# BMSV1_1.net
KiCad netlist of a schematic drawn in EAGLE
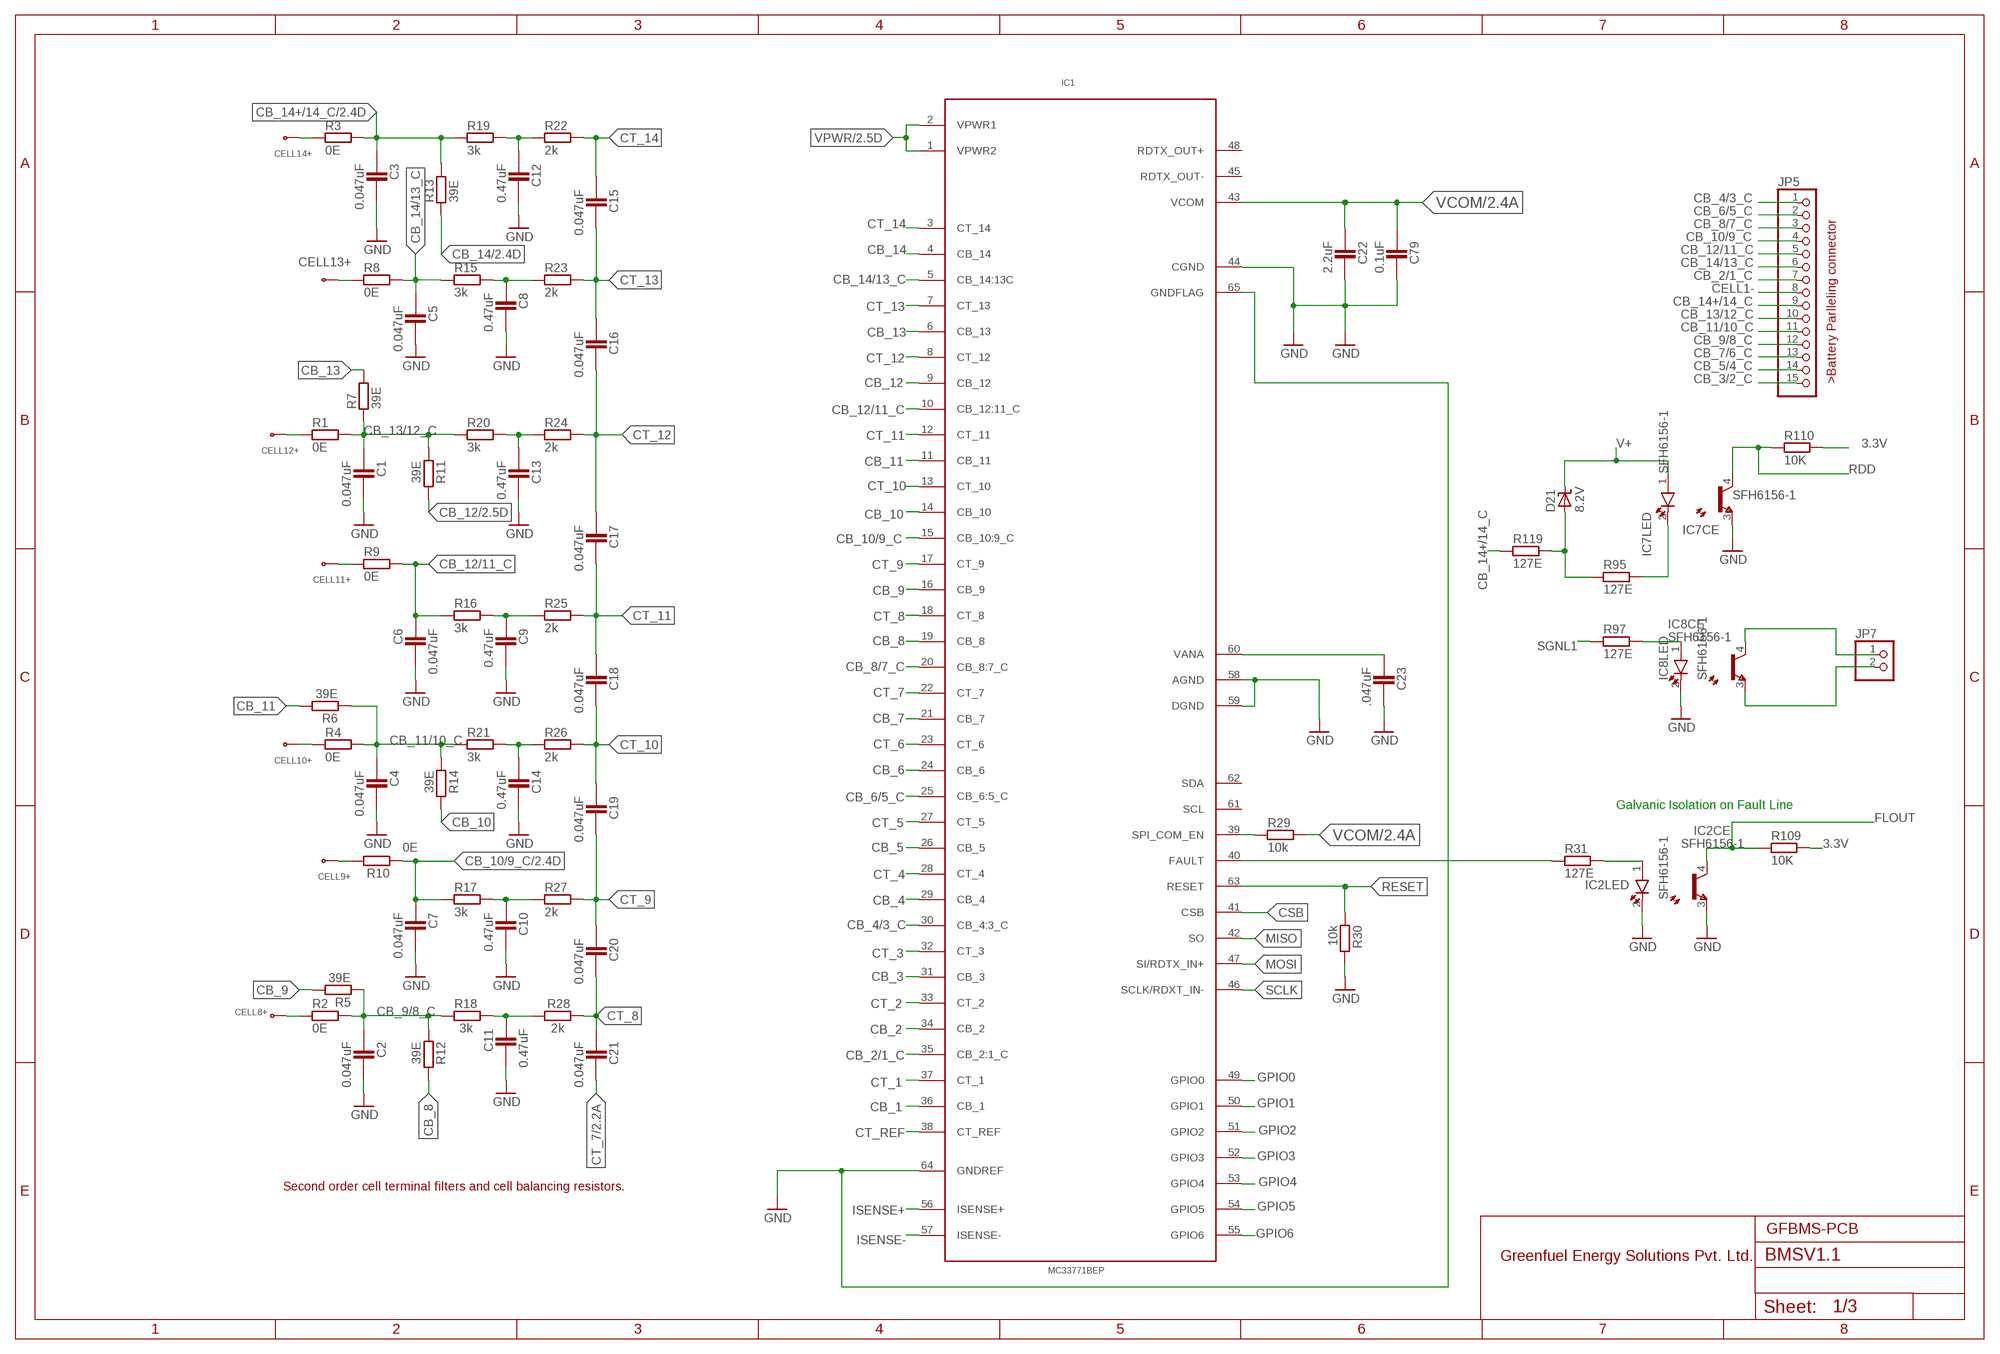
[diagram p0: schematic, sheet 1]
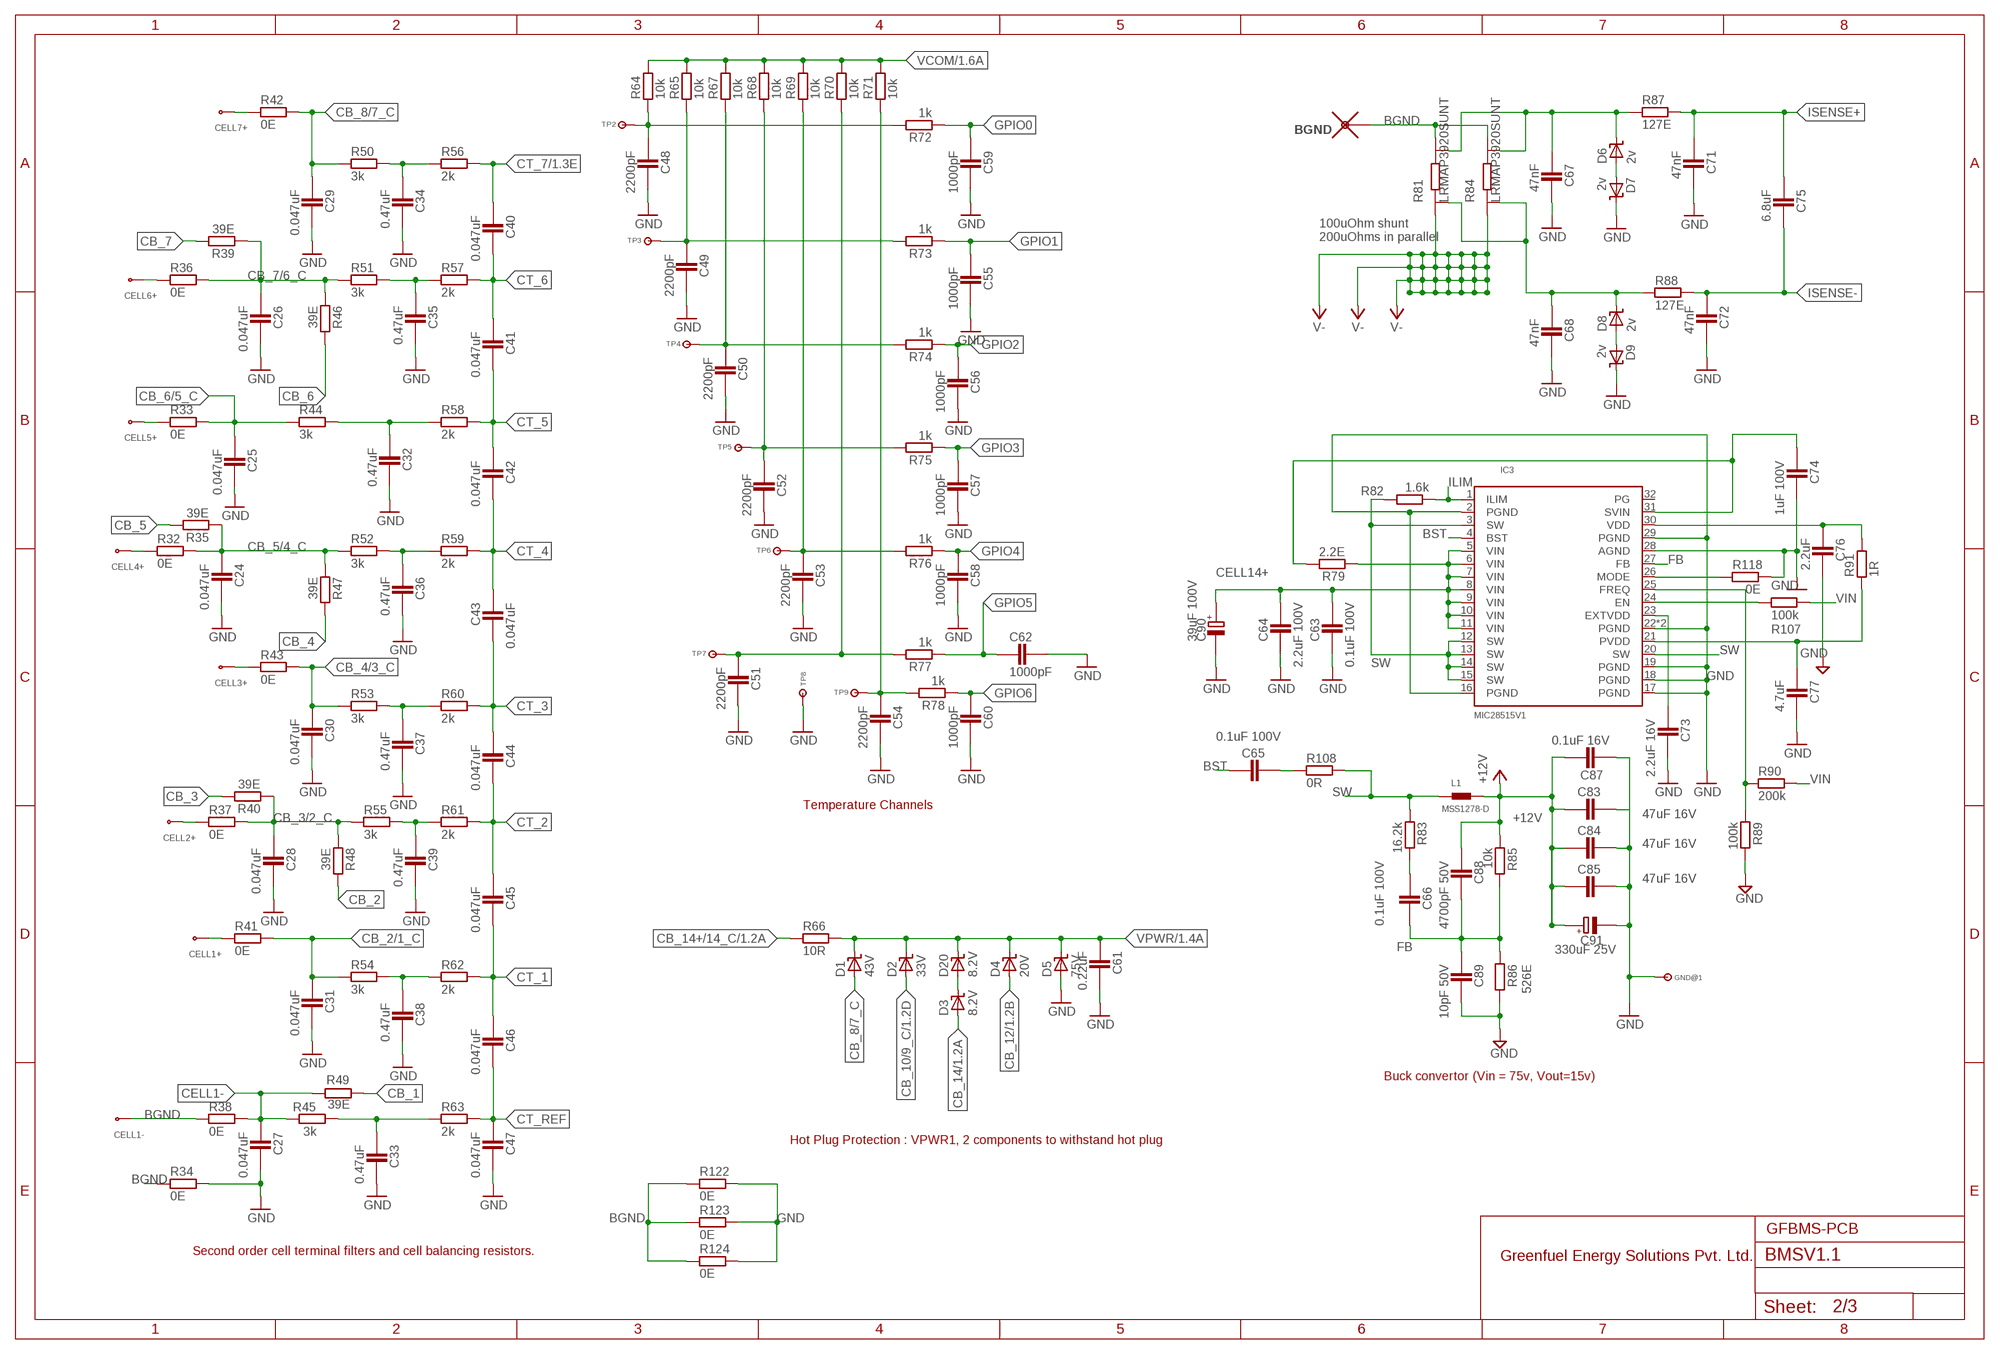
[diagram p1: schematic, sheet 2]
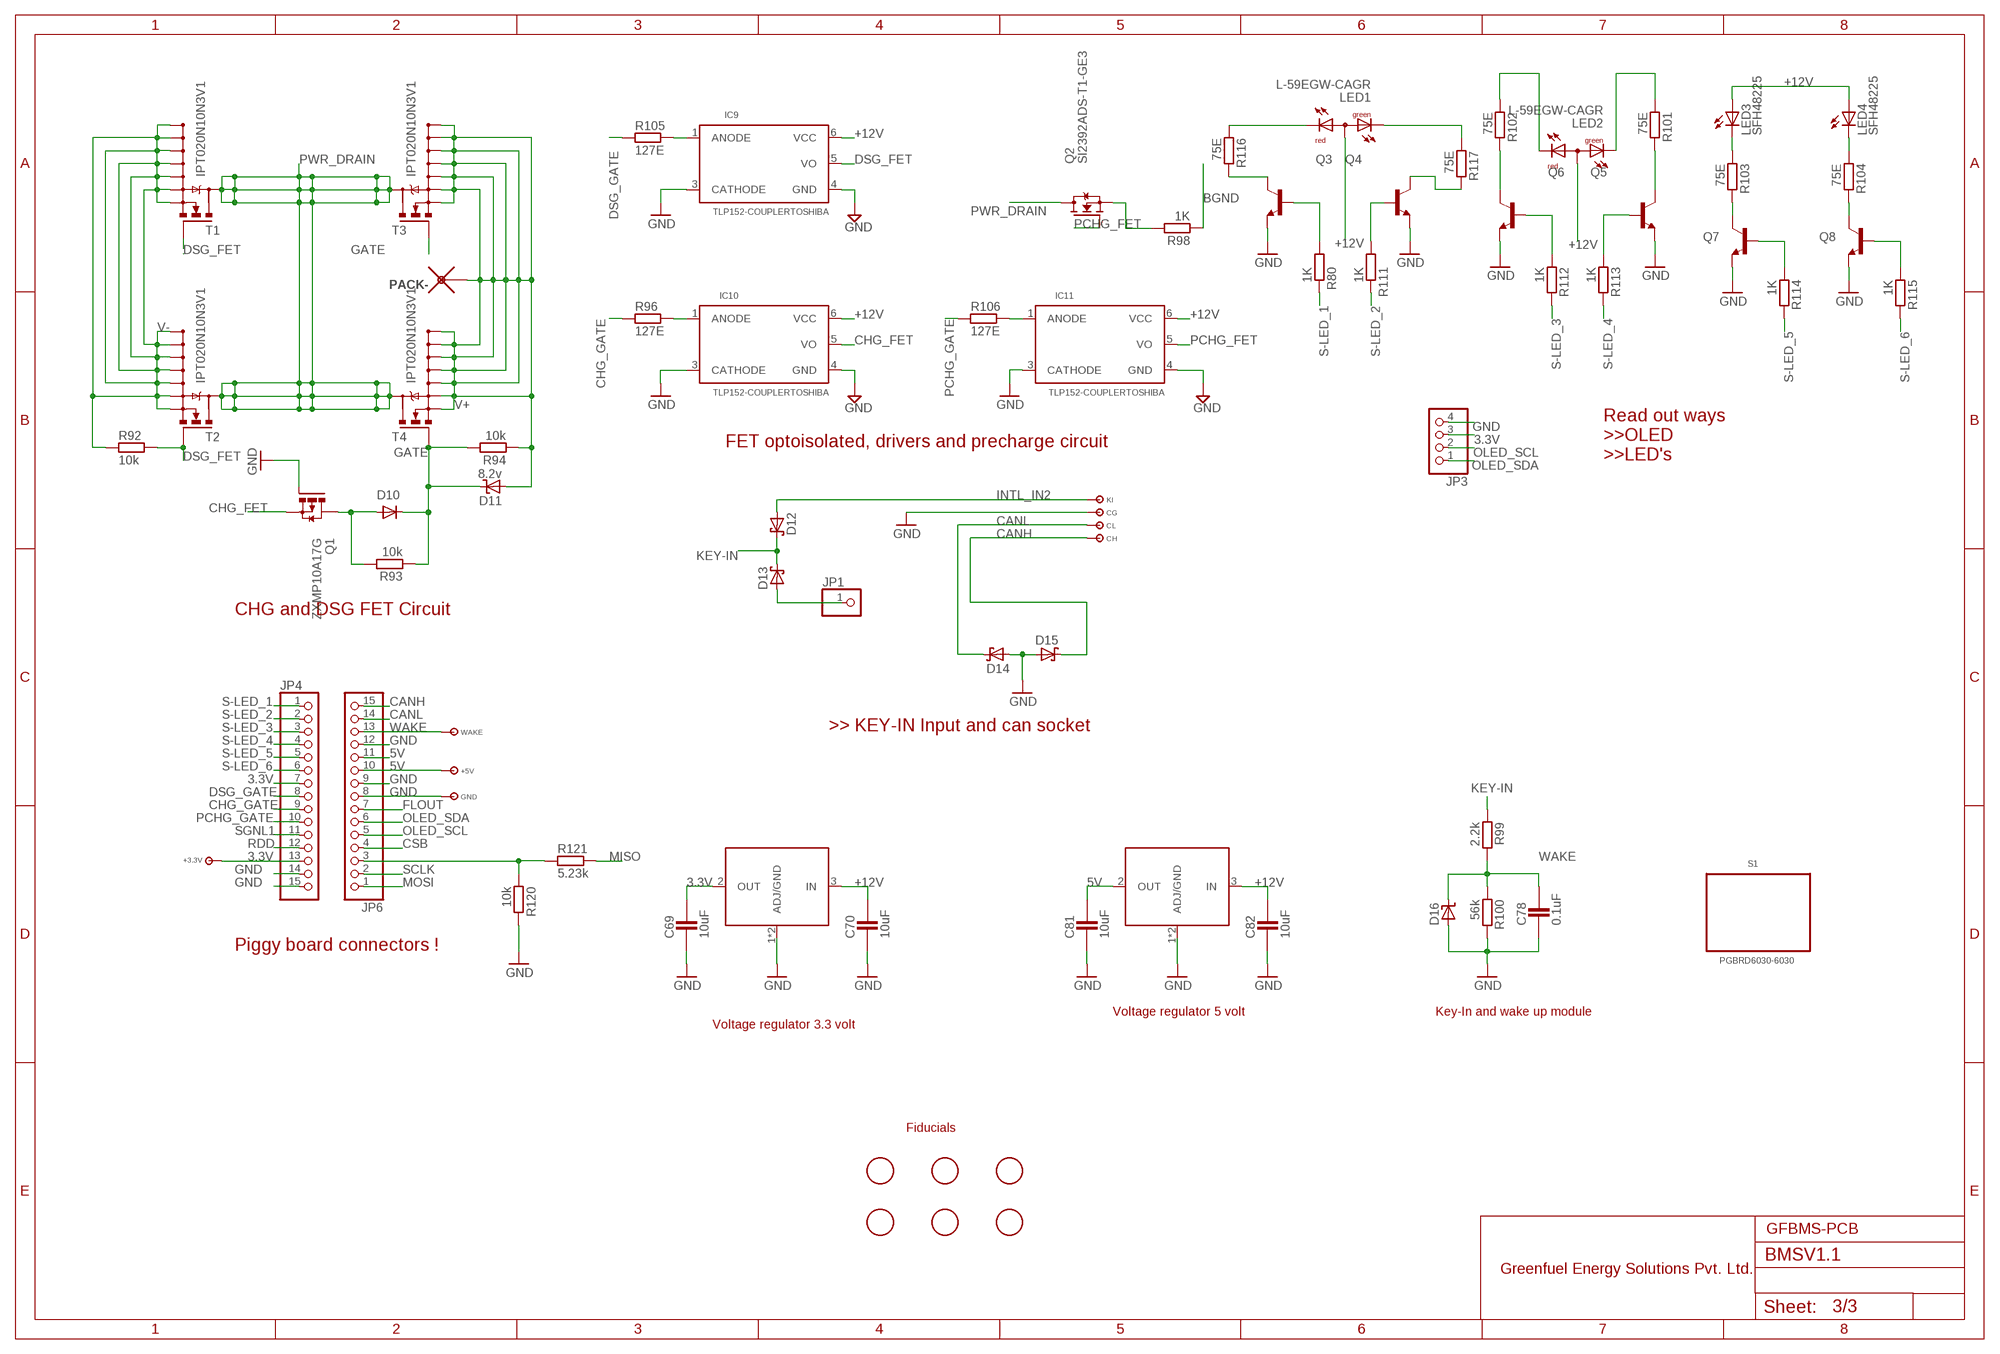
[diagram p2: schematic, sheet 3]

(export (version "E")
  (design (tool "Eeschema 10.0.6"))
  (components
    (comp (ref "+3.3V")
      (value "TP-SMD60")
      (footprint "eagle-import:TP-SMD60")
      (libsource (lib "eagle-import") (part "TP-SMD60"))
    )
    (comp (ref "+5V")
      (value "TP-SMD60")
      (footprint "eagle-import:TP-SMD60")
      (libsource (lib "eagle-import") (part "TP-SMD60"))
    )
    (comp (ref "C69")
      (value "10uF")
      (footprint "eagle-import:CAPC2012X145AN")
      (libsource (lib "eagle-import") (part "CAPACITOR_0805"))
    )
    (comp (ref "C70")
      (value "10uF")
      (footprint "eagle-import:CAPC2012X145AN")
      (libsource (lib "eagle-import") (part "CAPACITOR_0805"))
    )
    (comp (ref "C78")
      (value "0.1uF")
      (footprint "eagle-import:CAPC1608X92N")
      (libsource (lib "eagle-import") (part "CAPACITOR_0603"))
    )
    (comp (ref "C81")
      (value "10uF")
      (footprint "eagle-import:CAPC2012X145AN")
      (libsource (lib "eagle-import") (part "CAPACITOR_0805"))
    )
    (comp (ref "C82")
      (value "10uF")
      (footprint "eagle-import:CAPC2012X145AN")
      (libsource (lib "eagle-import") (part "CAPACITOR_0805"))
    )
    (comp (ref "CG")
      (value "TPTH7035")
      (footprint "eagle-import:TP7035")
      (libsource (lib "eagle-import") (part "TPTH7035"))
    )
    (comp (ref "CH")
      (value "TPTH7035")
      (footprint "eagle-import:TP7035")
      (libsource (lib "eagle-import") (part "TPTH7035"))
    )
    (comp (ref "CL")
      (value "TPTH7035")
      (footprint "eagle-import:TP7035")
      (libsource (lib "eagle-import") (part "TPTH7035"))
    )
    (comp (ref "D10")
      (value "DIODE_SOD-123")
      (footprint "eagle-import:SOD3718X135N")
      (libsource (lib "eagle-import") (part "DIODE_SOD-123"))
    )
    (comp (ref "D11")
      (value "8.2v")
      (footprint "eagle-import:SOD3718X135N")
      (libsource (lib "eagle-import") (part "ZENER_SOD-123"))
    )
    (comp (ref "D12")
      (value "SCHOTTKY_SOD-123")
      (footprint "eagle-import:SOD3718X135N")
      (libsource (lib "eagle-import") (part "SCHOTTKY_SOD-123"))
    )
    (comp (ref "D13")
      (value "SCHOTTKY_SOD-123")
      (footprint "eagle-import:SOD3718X135N")
      (libsource (lib "eagle-import") (part "SCHOTTKY_SOD-123"))
    )
    (comp (ref "D14")
      (value "SCHOTTKY_SOD-123")
      (footprint "eagle-import:SOD3718X135N")
      (libsource (lib "eagle-import") (part "SCHOTTKY_SOD-123"))
    )
    (comp (ref "D15")
      (value "SCHOTTKY_SOD-123")
      (footprint "eagle-import:SOD3718X135N")
      (libsource (lib "eagle-import") (part "SCHOTTKY_SOD-123"))
    )
    (comp (ref "D16")
      (value "ZENER_SOD-323")
      (footprint "eagle-import:SOD2514X100N")
      (libsource (lib "eagle-import") (part "ZENER_SOD-323"))
    )
    (comp (ref "FD1")
      (value "FIDUCIAL")
      (footprint "eagle-import:FIDUCIAL_1MM")
      (libsource (lib "eagle-import") (part "FIDUCIAL"))
    )
    (comp (ref "FD2")
      (value "FIDUCIAL")
      (footprint "eagle-import:FIDUCIAL_1MM")
      (libsource (lib "eagle-import") (part "FIDUCIAL"))
    )
    (comp (ref "FD3")
      (value "FIDUCIAL")
      (footprint "eagle-import:FIDUCIAL_1MM")
      (libsource (lib "eagle-import") (part "FIDUCIAL"))
    )
    (comp (ref "FD4")
      (value "FIDUCIAL")
      (footprint "eagle-import:FIDUCIAL_1MM")
      (libsource (lib "eagle-import") (part "FIDUCIAL"))
    )
    (comp (ref "FD5")
      (value "FIDUCIAL")
      (footprint "eagle-import:FIDUCIAL_1MM")
      (libsource (lib "eagle-import") (part "FIDUCIAL"))
    )
    (comp (ref "FD6")
      (value "FIDUCIAL")
      (footprint "eagle-import:FIDUCIAL_1MM")
      (libsource (lib "eagle-import") (part "FIDUCIAL"))
    )
    (comp (ref "GND")
      (value "TP-SMD60")
      (footprint "eagle-import:TP-SMD60")
      (libsource (lib "eagle-import") (part "TP-SMD60"))
    )
    (comp (ref "IC9")
      (value "TLP152-COUPLERTOSHIBA")
      (footprint "eagle-import:SO6-5PIN")
      (libsource (lib "eagle-import") (part "TLP152-COUPLERTOSHIBA"))
    )
    (comp (ref "IC10")
      (value "TLP152-COUPLERTOSHIBA")
      (footprint "eagle-import:SO6-5PIN")
      (libsource (lib "eagle-import") (part "TLP152-COUPLERTOSHIBA"))
    )
    (comp (ref "IC11")
      (value "TLP152-COUPLERTOSHIBA")
      (footprint "eagle-import:SO6-5PIN")
      (libsource (lib "eagle-import") (part "TLP152-COUPLERTOSHIBA"))
    )
    (comp (ref "JP1")
      (value "PINHD-1X1CB")
      (footprint "eagle-import:1X01-CLEANBIG")
      (libsource (lib "eagle-import") (part "PINHD-1X1CB"))
    )
    (comp (ref "JP3")
      (value "PINOLED-4")
      (footprint "eagle-import:OLED-CON")
      (libsource (lib "eagle-import") (part "PINOLED-4"))
    )
    (comp (ref "JP4")
      (value "PINHD-1X15")
      (footprint "eagle-import:1X15")
      (libsource (lib "eagle-import") (part "PINHD-1X15"))
    )
    (comp (ref "JP6")
      (value "PINHD-1X15")
      (footprint "eagle-import:1X15")
      (libsource (lib "eagle-import") (part "PINHD-1X15"))
    )
    (comp (ref "KI")
      (value "TPTH7035")
      (footprint "eagle-import:TP7035")
      (libsource (lib "eagle-import") (part "TPTH7035"))
    )
    (comp (ref "LED1")
      (value "L-59EGW-CAGR")
      (footprint "eagle-import:L-59EGW-CA")
      (libsource (lib "eagle-import") (part "L-59EGW-CAGR"))
    )
    (comp (ref "LED2")
      (value "L-59EGW-CAGR")
      (footprint "eagle-import:L-59EGW-CA")
      (libsource (lib "eagle-import") (part "L-59EGW-CAGR"))
    )
    (comp (ref "LED3")
      (value "SFH48225")
      (footprint "eagle-import:SFH482")
      (libsource (lib "eagle-import") (part "SFH48225"))
    )
    (comp (ref "LED4")
      (value "SFH48225")
      (footprint "eagle-import:SFH482")
      (libsource (lib "eagle-import") (part "SFH48225"))
    )
    (comp (ref "PACK-")
      (value "WPAD")
      (footprint "eagle-import:WPAD")
      (libsource (lib "eagle-import") (part "WPAD"))
    )
    (comp (ref "Q1")
      (value "ZXMP10A17G")
      (footprint "eagle-import:SOT23-3")
      (libsource (lib "eagle-import") (part "ZXMP10A17G"))
    )
    (comp (ref "Q2")
      (value "SI2392ADS-T1-GE3")
      (footprint "eagle-import:SOT23-3")
      (libsource (lib "eagle-import") (part "BSS138"))
    )
    (comp (ref "Q3")
      (value "NPN_SOT-23")
      (footprint "eagle-import:SOT95P280X135-3N")
      (libsource (lib "eagle-import") (part "NPN_SOT-23"))
    )
    (comp (ref "Q4")
      (value "NPN_SOT-23")
      (footprint "eagle-import:SOT95P280X135-3N")
      (libsource (lib "eagle-import") (part "NPN_SOT-23"))
    )
    (comp (ref "Q5")
      (value "NPN_SOT-23")
      (footprint "eagle-import:SOT95P280X135-3N")
      (libsource (lib "eagle-import") (part "NPN_SOT-23"))
    )
    (comp (ref "Q6")
      (value "NPN_SOT-23")
      (footprint "eagle-import:SOT95P280X135-3N")
      (libsource (lib "eagle-import") (part "NPN_SOT-23"))
    )
    (comp (ref "Q7")
      (value "NPN_SOT-23")
      (footprint "eagle-import:SOT95P280X135-3N")
      (libsource (lib "eagle-import") (part "NPN_SOT-23"))
    )
    (comp (ref "Q8")
      (value "NPN_SOT-23")
      (footprint "eagle-import:SOT95P280X135-3N")
      (libsource (lib "eagle-import") (part "NPN_SOT-23"))
    )
    (comp (ref "R80")
      (value "1K")
      (footprint "eagle-import:RESC1005X40AN")
      (libsource (lib "eagle-import") (part "RESISTOR_0402"))
    )
    (comp (ref "R92")
      (value "10k")
      (footprint "eagle-import:RESC1005X40AN")
      (libsource (lib "eagle-import") (part "RESISTOR_0402"))
    )
    (comp (ref "R93")
      (value "10k")
      (footprint "eagle-import:RESC1005X40AN")
      (libsource (lib "eagle-import") (part "RESISTOR_0402"))
    )
    (comp (ref "R94")
      (value "10k")
      (footprint "eagle-import:RESC1005X40AN")
      (libsource (lib "eagle-import") (part "RESISTOR_0402"))
    )
    (comp (ref "R96")
      (value "127E")
      (footprint "eagle-import:RESC1608X55N")
      (libsource (lib "eagle-import") (part "RESISTOR_0603"))
    )
    (comp (ref "R98")
      (value "1K")
      (footprint "eagle-import:RESC5025X70N")
      (libsource (lib "eagle-import") (part "RESISTOR_2010"))
    )
    (comp (ref "R99")
      (value "2.2k")
      (footprint "eagle-import:RESC1608X55N")
      (libsource (lib "eagle-import") (part "RESISTOR_0603"))
    )
    (comp (ref "R100")
      (value "56k")
      (footprint "eagle-import:RESC1608X55N")
      (libsource (lib "eagle-import") (part "RESISTOR_0603"))
    )
    (comp (ref "R101")
      (value "75E")
      (footprint "eagle-import:RESC1005X40AN")
      (libsource (lib "eagle-import") (part "RESISTOR_0402"))
    )
    (comp (ref "R102")
      (value "75E")
      (footprint "eagle-import:RESC1005X40AN")
      (libsource (lib "eagle-import") (part "RESISTOR_0402"))
    )
    (comp (ref "R103")
      (value "75E")
      (footprint "eagle-import:RESC1005X40AN")
      (libsource (lib "eagle-import") (part "RESISTOR_0402"))
    )
    (comp (ref "R104")
      (value "75E")
      (footprint "eagle-import:RESC1005X40AN")
      (libsource (lib "eagle-import") (part "RESISTOR_0402"))
    )
    (comp (ref "R105")
      (value "127E")
      (footprint "eagle-import:RESC1608X55N")
      (libsource (lib "eagle-import") (part "RESISTOR_0603"))
    )
    (comp (ref "R106")
      (value "127E")
      (footprint "eagle-import:RESC1608X55N")
      (libsource (lib "eagle-import") (part "RESISTOR_0603"))
    )
    (comp (ref "R111")
      (value "1K")
      (footprint "eagle-import:RESC1005X40AN")
      (libsource (lib "eagle-import") (part "RESISTOR_0402"))
    )
    (comp (ref "R112")
      (value "1K")
      (footprint "eagle-import:RESC1005X40AN")
      (libsource (lib "eagle-import") (part "RESISTOR_0402"))
    )
    (comp (ref "R113")
      (value "1K")
      (footprint "eagle-import:RESC1005X40AN")
      (libsource (lib "eagle-import") (part "RESISTOR_0402"))
    )
    (comp (ref "R114")
      (value "1K")
      (footprint "eagle-import:RESC1005X40AN")
      (libsource (lib "eagle-import") (part "RESISTOR_0402"))
    )
    (comp (ref "R115")
      (value "1K")
      (footprint "eagle-import:RESC1005X40AN")
      (libsource (lib "eagle-import") (part "RESISTOR_0402"))
    )
    (comp (ref "R116")
      (value "75E")
      (footprint "eagle-import:RESC1005X40AN")
      (libsource (lib "eagle-import") (part "RESISTOR_0402"))
    )
    (comp (ref "R117")
      (value "75E")
      (footprint "eagle-import:RESC1005X40AN")
      (libsource (lib "eagle-import") (part "RESISTOR_0402"))
    )
    (comp (ref "R120")
      (value "10k")
      (footprint "eagle-import:RESC1608X55N")
      (libsource (lib "eagle-import") (part "RESISTOR_0603"))
    )
    (comp (ref "R121")
      (value "5.23k")
      (footprint "eagle-import:RESC1608X55N")
      (libsource (lib "eagle-import") (part "RESISTOR_0603"))
    )
    (comp (ref "S1")
      (value "PGBRD6030-6030")
      (footprint "eagle-import:PIG6030")
      (libsource (lib "eagle-import") (part "PGBRD6030-6030"))
    )
    (comp (ref "T1")
      (value "IPT020N10N3V1")
      (footprint "eagle-import:PG-HSOF-9")
      (libsource (lib "eagle-import") (part "IPT020N10N3V1"))
    )
    (comp (ref "T2")
      (value "IPT020N10N3V1")
      (footprint "eagle-import:PG-HSOF-9")
      (libsource (lib "eagle-import") (part "IPT020N10N3V1"))
    )
    (comp (ref "T3")
      (value "IPT020N10N3V1")
      (footprint "eagle-import:PG-HSOF-9")
      (libsource (lib "eagle-import") (part "IPT020N10N3V1"))
    )
    (comp (ref "T4")
      (value "IPT020N10N3V1")
      (footprint "eagle-import:PG-HSOF-9")
      (libsource (lib "eagle-import") (part "IPT020N10N3V1"))
    )
    (comp (ref "U1")
      (value "NCV1117ST33T3G")
      (footprint "eagle-import:SOT-223")
      (libsource (lib "eagle-import") (part "NCP1117LP-PG"))
    )
    (comp (ref "U2")
      (value "NCV1117ST50T3G")
      (footprint "eagle-import:SOT-223")
      (libsource (lib "eagle-import") (part "NCP1117LP-PG"))
    )
    (comp (ref "WAKE")
      (value "TP-SMD60")
      (footprint "eagle-import:TP-SMD60")
      (libsource (lib "eagle-import") (part "TP-SMD60"))
    )
    (comp (ref "BGND")
      (value "WPAD")
      (footprint "eagle-import:WPAD")
      (libsource (lib "eagle-import") (part "WPAD"))
    )
    (comp (ref "C24")
      (value "0.047uF")
      (footprint "eagle-import:CAPC1608X92N")
      (libsource (lib "eagle-import") (part "CAPACITOR_0603"))
    )
    (comp (ref "C25")
      (value "0.047uF")
      (footprint "eagle-import:CAPC1608X92N")
      (libsource (lib "eagle-import") (part "CAPACITOR_0603"))
    )
    (comp (ref "C26")
      (value "0.047uF")
      (footprint "eagle-import:CAPC1608X92N")
      (libsource (lib "eagle-import") (part "CAPACITOR_0603"))
    )
    (comp (ref "C27")
      (value "0.047uF")
      (footprint "eagle-import:CAPC1608X92N")
      (libsource (lib "eagle-import") (part "CAPACITOR_0603"))
    )
    (comp (ref "C28")
      (value "0.047uF")
      (footprint "eagle-import:CAPC1608X92N")
      (libsource (lib "eagle-import") (part "CAPACITOR_0603"))
    )
    (comp (ref "C29")
      (value "0.047uF")
      (footprint "eagle-import:CAPC1608X92N")
      (libsource (lib "eagle-import") (part "CAPACITOR_0603"))
    )
    (comp (ref "C30")
      (value "0.047uF")
      (footprint "eagle-import:CAPC1608X92N")
      (libsource (lib "eagle-import") (part "CAPACITOR_0603"))
    )
    (comp (ref "C31")
      (value "0.047uF")
      (footprint "eagle-import:CAPC1608X92N")
      (libsource (lib "eagle-import") (part "CAPACITOR_0603"))
    )
    (comp (ref "C32")
      (value "0.47uF")
      (footprint "eagle-import:CAPC3215X168N")
      (libsource (lib "eagle-import") (part "CAPACITOR_1206"))
    )
    (comp (ref "C33")
      (value "0.47uF")
      (footprint "eagle-import:CAPC3215X168N")
      (libsource (lib "eagle-import") (part "CAPACITOR_1206"))
    )
    (comp (ref "C34")
      (value "0.47uF")
      (footprint "eagle-import:CAPC3215X168N")
      (libsource (lib "eagle-import") (part "CAPACITOR_1206"))
    )
    (comp (ref "C35")
      (value "0.47uF")
      (footprint "eagle-import:CAPC3215X168N")
      (libsource (lib "eagle-import") (part "CAPACITOR_1206"))
    )
    (comp (ref "C36")
      (value "0.47uF")
      (footprint "eagle-import:CAPC3215X168N")
      (libsource (lib "eagle-import") (part "CAPACITOR_1206"))
    )
    (comp (ref "C37")
      (value "0.47uF")
      (footprint "eagle-import:CAPC3215X168N")
      (libsource (lib "eagle-import") (part "CAPACITOR_1206"))
    )
    (comp (ref "C38")
      (value "0.47uF")
      (footprint "eagle-import:CAPC3215X168N")
      (libsource (lib "eagle-import") (part "CAPACITOR_1206"))
    )
    (comp (ref "C39")
      (value "0.47uF")
      (footprint "eagle-import:CAPC3215X168N")
      (libsource (lib "eagle-import") (part "CAPACITOR_1206"))
    )
    (comp (ref "C40")
      (value "0.047uF")
      (footprint "eagle-import:CAPC1005X60N")
      (libsource (lib "eagle-import") (part "CAPACITOR_0402"))
    )
    (comp (ref "C41")
      (value "0.047uF")
      (footprint "eagle-import:CAPC1005X60N")
      (libsource (lib "eagle-import") (part "CAPACITOR_0402"))
    )
    (comp (ref "C42")
      (value "0.047uF")
      (footprint "eagle-import:CAPC1005X60N")
      (libsource (lib "eagle-import") (part "CAPACITOR_0402"))
    )
    (comp (ref "C43")
      (value "0.047uF")
      (footprint "eagle-import:CAPC1005X60N")
      (libsource (lib "eagle-import") (part "CAPACITOR_0402"))
    )
    (comp (ref "C44")
      (value "0.047uF")
      (footprint "eagle-import:CAPC1005X60N")
      (libsource (lib "eagle-import") (part "CAPACITOR_0402"))
    )
    (comp (ref "C45")
      (value "0.047uF")
      (footprint "eagle-import:CAPC1005X60N")
      (libsource (lib "eagle-import") (part "CAPACITOR_0402"))
    )
    (comp (ref "C46")
      (value "0.047uF")
      (footprint "eagle-import:CAPC1005X60N")
      (libsource (lib "eagle-import") (part "CAPACITOR_0402"))
    )
    (comp (ref "C47")
      (value "0.047uF")
      (footprint "eagle-import:CAPC1005X60N")
      (libsource (lib "eagle-import") (part "CAPACITOR_0402"))
    )
    (comp (ref "C48")
      (value "2200pF")
      (footprint "eagle-import:CAPC1005X60N")
      (libsource (lib "eagle-import") (part "CAPACITOR_0402"))
    )
    (comp (ref "C49")
      (value "2200pF")
      (footprint "eagle-import:CAPC1005X60N")
      (libsource (lib "eagle-import") (part "CAPACITOR_0402"))
    )
    (comp (ref "C50")
      (value "2200pF")
      (footprint "eagle-import:CAPC1005X60N")
      (libsource (lib "eagle-import") (part "CAPACITOR_0402"))
    )
    (comp (ref "C51")
      (value "2200pF")
      (footprint "eagle-import:CAPC1005X60N")
      (libsource (lib "eagle-import") (part "CAPACITOR_0402"))
    )
    (comp (ref "C52")
      (value "2200pF")
      (footprint "eagle-import:CAPC1005X60N")
      (libsource (lib "eagle-import") (part "CAPACITOR_0402"))
    )
    (comp (ref "C53")
      (value "2200pF")
      (footprint "eagle-import:CAPC1005X60N")
      (libsource (lib "eagle-import") (part "CAPACITOR_0402"))
    )
    (comp (ref "C54")
      (value "2200pF")
      (footprint "eagle-import:CAPC1005X60N")
      (libsource (lib "eagle-import") (part "CAPACITOR_0402"))
    )
    (comp (ref "C55")
      (value "1000pF")
      (footprint "eagle-import:CAPC1005X60N")
      (libsource (lib "eagle-import") (part "CAPACITOR_0402"))
    )
    (comp (ref "C56")
      (value "1000pF")
      (footprint "eagle-import:CAPC1005X60N")
      (libsource (lib "eagle-import") (part "CAPACITOR_0402"))
    )
    (comp (ref "C57")
      (value "1000pF")
      (footprint "eagle-import:CAPC1005X60N")
      (libsource (lib "eagle-import") (part "CAPACITOR_0402"))
    )
    (comp (ref "C58")
      (value "1000pF")
      (footprint "eagle-import:CAPC1005X60N")
      (libsource (lib "eagle-import") (part "CAPACITOR_0402"))
    )
    (comp (ref "C59")
      (value "1000pF")
      (footprint "eagle-import:CAPC1005X60N")
      (libsource (lib "eagle-import") (part "CAPACITOR_0402"))
    )
    (comp (ref "C60")
      (value "1000pF")
      (footprint "eagle-import:CAPC1005X60N")
      (libsource (lib "eagle-import") (part "CAPACITOR_0402"))
    )
    (comp (ref "C61")
      (value "0.22uF")
      (footprint "eagle-import:CAPC2012X145AN")
      (libsource (lib "eagle-import") (part "CAPACITOR_0805"))
    )
    (comp (ref "C62")
      (value "1000pF")
      (footprint "eagle-import:CAPC1005X60N")
      (libsource (lib "eagle-import") (part "CAPACITOR_0402"))
    )
    (comp (ref "C63")
      (value "0.1uF 100V")
      (footprint "eagle-import:CAPC1608X92N")
      (libsource (lib "eagle-import") (part "CAPACITOR_0603"))
    )
    (comp (ref "C64")
      (value "2.2uF 100V")
      (footprint "eagle-import:CAPC3225X168N")
      (libsource (lib "eagle-import") (part "CAPACITOR_1210"))
    )
    (comp (ref "C65")
      (value "0.1uF 100V")
      (footprint "eagle-import:CAPC1608X92N")
      (libsource (lib "eagle-import") (part "CAPACITOR_0603"))
    )
    (comp (ref "C66")
      (value "0.1uF 100V")
      (footprint "eagle-import:CAPC1608X92N")
      (libsource (lib "eagle-import") (part "CAPACITOR_0603"))
    )
    (comp (ref "C67")
      (value "47nF")
      (footprint "eagle-import:CAPC1608X92N")
      (libsource (lib "eagle-import") (part "CAPACITOR_0603"))
    )
    (comp (ref "C68")
      (value "47nF")
      (footprint "eagle-import:CAPC1608X92N")
      (libsource (lib "eagle-import") (part "CAPACITOR_0603"))
    )
    (comp (ref "C71")
      (value "47nF")
      (footprint "eagle-import:CAPC1005X60N")
      (libsource (lib "eagle-import") (part "CAPACITOR_0402"))
    )
    (comp (ref "C72")
      (value "47nF")
      (footprint "eagle-import:CAPC1005X60N")
      (libsource (lib "eagle-import") (part "CAPACITOR_0402"))
    )
    (comp (ref "C73")
      (value "2.2uF 16V")
      (footprint "eagle-import:CAPC1608X92N")
      (libsource (lib "eagle-import") (part "CAPACITOR_0603"))
    )
    (comp (ref "C74")
      (value "1uF 100V")
      (footprint "eagle-import:CAPC2012X145AN")
      (libsource (lib "eagle-import") (part "CAPACITOR_0805"))
    )
    (comp (ref "C75")
      (value "6.8uF")
      (footprint "eagle-import:CAPC2012X145AN")
      (libsource (lib "eagle-import") (part "CAPACITOR_0805"))
    )
    (comp (ref "C76")
      (value "2.2uF")
      (footprint "eagle-import:CAPC1608X92N")
      (libsource (lib "eagle-import") (part "CAPACITOR_0603"))
    )
    (comp (ref "C77")
      (value "4.7uF")
      (footprint "eagle-import:CAPC2012X145AN")
      (libsource (lib "eagle-import") (part "CAPACITOR_0805"))
    )
    (comp (ref "C83")
      (value "47uF 16V")
      (footprint "eagle-import:CAPC3225X168N")
      (libsource (lib "eagle-import") (part "CAPACITOR_1210"))
    )
    (comp (ref "C84")
      (value "47uF 16V")
      (footprint "eagle-import:CAPC3225X168N")
      (libsource (lib "eagle-import") (part "CAPACITOR_1210"))
    )
    (comp (ref "C85")
      (value "47uF 16V")
      (footprint "eagle-import:CAPC3225X168N")
      (libsource (lib "eagle-import") (part "CAPACITOR_1210"))
    )
    (comp (ref "C87")
      (value "0.1uF 16V")
      (footprint "eagle-import:CAPC1608X92N")
      (libsource (lib "eagle-import") (part "CAPACITOR_0603"))
    )
    (comp (ref "C88")
      (value "4700pF 50V")
      (footprint "eagle-import:CAPC1608X92N")
      (libsource (lib "eagle-import") (part "CAPACITOR_0603"))
    )
    (comp (ref "C89")
      (value "10pF 50V")
      (footprint "eagle-import:CAPC1608X92N")
      (libsource (lib "eagle-import") (part "CAPACITOR_0603"))
    )
    (comp (ref "C90")
      (value "39uF 100V")
      (footprint "eagle-import:CAPAE830X1020N")
      (libsource (lib "eagle-import") (part "POLARISED_CASE_F"))
    )
    (comp (ref "C91")
      (value "330uF 25V")
      (footprint "eagle-import:CAPAE830X1020N")
      (libsource (lib "eagle-import") (part "POLARISED_CASE_F"))
    )
    (comp (ref "CELL1+")
      (value "GF_BMS_CELL_PADP_PAD")
      (footprint "eagle-import:CELL_PAD")
      (libsource (lib "eagle-import") (part "GF_BMS_CELL_PADP_PAD"))
    )
    (comp (ref "CELL1-")
      (value "GF_BMS_CELL_PADP_PAD")
      (footprint "eagle-import:CELL_PAD")
      (libsource (lib "eagle-import") (part "GF_BMS_CELL_PADP_PAD"))
    )
    (comp (ref "CELL2+")
      (value "GF_BMS_CELL_PADP_PAD")
      (footprint "eagle-import:CELL_PAD")
      (libsource (lib "eagle-import") (part "GF_BMS_CELL_PADP_PAD"))
    )
    (comp (ref "CELL3+")
      (value "GF_BMS_CELL_PADP_PAD")
      (footprint "eagle-import:CELL_PAD")
      (libsource (lib "eagle-import") (part "GF_BMS_CELL_PADP_PAD"))
    )
    (comp (ref "CELL4+")
      (value "GF_BMS_CELL_PADP_PAD")
      (footprint "eagle-import:CELL_PAD")
      (libsource (lib "eagle-import") (part "GF_BMS_CELL_PADP_PAD"))
    )
    (comp (ref "CELL5+")
      (value "GF_BMS_CELL_PADP_PAD")
      (footprint "eagle-import:CELL_PAD")
      (libsource (lib "eagle-import") (part "GF_BMS_CELL_PADP_PAD"))
    )
    (comp (ref "CELL6+")
      (value "GF_BMS_CELL_PADP_PAD")
      (footprint "eagle-import:CELL_PAD")
      (libsource (lib "eagle-import") (part "GF_BMS_CELL_PADP_PAD"))
    )
    (comp (ref "CELL7+")
      (value "GF_BMS_CELL_PADP_PAD")
      (footprint "eagle-import:CELL_PAD")
      (libsource (lib "eagle-import") (part "GF_BMS_CELL_PADP_PAD"))
    )
    (comp (ref "D1")
      (value "43V")
      (footprint "eagle-import:SOD2514X100N")
      (libsource (lib "eagle-import") (part "ZENER_SOD-323"))
    )
    (comp (ref "D2")
      (value "33V")
      (footprint "eagle-import:SOD3718X135N")
      (libsource (lib "eagle-import") (part "ZENER_SOD-123"))
    )
    (comp (ref "D3")
      (value "8.2V")
      (footprint "eagle-import:SOD3718X135N")
      (libsource (lib "eagle-import") (part "ZENER_SOD-123"))
    )
    (comp (ref "D4")
      (value "20V")
      (footprint "eagle-import:SOD3718X135N")
      (libsource (lib "eagle-import") (part "ZENER_SOD-123"))
    )
    (comp (ref "D5")
      (value "75V")
      (footprint "eagle-import:SOD3718X135N")
      (libsource (lib "eagle-import") (part "ZENER_SOD-123"))
    )
    (comp (ref "D6")
      (value "2v")
      (footprint "eagle-import:SOD3718X135N")
      (libsource (lib "eagle-import") (part "ZENER_SOD-123"))
    )
    (comp (ref "D7")
      (value "2v")
      (footprint "eagle-import:SOD3718X135N")
      (libsource (lib "eagle-import") (part "ZENER_SOD-123"))
    )
    (comp (ref "D8")
      (value "2v")
      (footprint "eagle-import:SOD3718X135N")
      (libsource (lib "eagle-import") (part "ZENER_SOD-123"))
    )
    (comp (ref "D9")
      (value "2v")
      (footprint "eagle-import:SOD3718X135N")
      (libsource (lib "eagle-import") (part "ZENER_SOD-123"))
    )
    (comp (ref "D20")
      (value "8.2V")
      (footprint "eagle-import:SOD3718X135N")
      (libsource (lib "eagle-import") (part "ZENER_SOD-123"))
    )
    (comp (ref "GND@1")
      (value "TP-SMD60")
      (footprint "eagle-import:TP-SMD60")
      (libsource (lib "eagle-import") (part "TP-SMD60"))
    )
    (comp (ref "IC3")
      (value "MIC28515V1")
      (footprint "eagle-import:VQFN-32")
      (libsource (lib "eagle-import") (part "MIC28515V1"))
    )
    (comp (ref "L1")
      (value "MSS1278-D")
      (footprint "eagle-import:MSS1278D_T")
      (libsource (lib "eagle-import") (part "MSS1278-D"))
    )
    (comp (ref "R32")
      (value "0E")
      (footprint "eagle-import:RESC1005X40AN")
      (libsource (lib "eagle-import") (part "RESISTOR_0402"))
    )
    (comp (ref "R33")
      (value "0E")
      (footprint "eagle-import:RESC1005X40AN")
      (libsource (lib "eagle-import") (part "RESISTOR_0402"))
    )
    (comp (ref "R34")
      (value "0E")
      (footprint "eagle-import:RESC1005X40AN")
      (libsource (lib "eagle-import") (part "RESISTOR_0402"))
    )
    (comp (ref "R35")
      (value "39E")
      (footprint "eagle-import:RESC3225X70N")
      (libsource (lib "eagle-import") (part "RESISTOR_1210"))
    )
    (comp (ref "R36")
      (value "0E")
      (footprint "eagle-import:RESC1005X40AN")
      (libsource (lib "eagle-import") (part "RESISTOR_0402"))
    )
    (comp (ref "R37")
      (value "0E")
      (footprint "eagle-import:RESC1005X40AN")
      (libsource (lib "eagle-import") (part "RESISTOR_0402"))
    )
    (comp (ref "R38")
      (value "0E")
      (footprint "eagle-import:RESC1005X40AN")
      (libsource (lib "eagle-import") (part "RESISTOR_0402"))
    )
    (comp (ref "R39")
      (value "39E")
      (footprint "eagle-import:RESC3225X70N")
      (libsource (lib "eagle-import") (part "RESISTOR_1210"))
    )
    (comp (ref "R40")
      (value "39E")
      (footprint "eagle-import:RESC3225X70N")
      (libsource (lib "eagle-import") (part "RESISTOR_1210"))
    )
    (comp (ref "R41")
      (value "0E")
      (footprint "eagle-import:RESC1005X40AN")
      (libsource (lib "eagle-import") (part "RESISTOR_0402"))
    )
    (comp (ref "R42")
      (value "0E")
      (footprint "eagle-import:RESC1005X40AN")
      (libsource (lib "eagle-import") (part "RESISTOR_0402"))
    )
    (comp (ref "R43")
      (value "0E")
      (footprint "eagle-import:RESC1005X40AN")
      (libsource (lib "eagle-import") (part "RESISTOR_0402"))
    )
    (comp (ref "R44")
      (value "3k")
      (footprint "eagle-import:RESC1005X40AN")
      (libsource (lib "eagle-import") (part "RESISTOR_0402"))
    )
    (comp (ref "R45")
      (value "3k")
      (footprint "eagle-import:RESC1005X40AN")
      (libsource (lib "eagle-import") (part "RESISTOR_0402"))
    )
    (comp (ref "R46")
      (value "39E")
      (footprint "eagle-import:RESC3225X70N")
      (libsource (lib "eagle-import") (part "RESISTOR_1210"))
    )
    (comp (ref "R47")
      (value "39E")
      (footprint "eagle-import:RESC3225X70N")
      (libsource (lib "eagle-import") (part "RESISTOR_1210"))
    )
    (comp (ref "R48")
      (value "39E")
      (footprint "eagle-import:RESC3225X70N")
      (libsource (lib "eagle-import") (part "RESISTOR_1210"))
    )
    (comp (ref "R49")
      (value "39E")
      (footprint "eagle-import:RESC3225X70N")
      (libsource (lib "eagle-import") (part "RESISTOR_1210"))
    )
    (comp (ref "R50")
      (value "3k")
      (footprint "eagle-import:RESC1005X40AN")
      (libsource (lib "eagle-import") (part "RESISTOR_0402"))
    )
    (comp (ref "R51")
      (value "3k")
      (footprint "eagle-import:RESC1005X40AN")
      (libsource (lib "eagle-import") (part "RESISTOR_0402"))
    )
    (comp (ref "R52")
      (value "3k")
      (footprint "eagle-import:RESC1005X40AN")
      (libsource (lib "eagle-import") (part "RESISTOR_0402"))
    )
    (comp (ref "R53")
      (value "3k")
      (footprint "eagle-import:RESC1005X40AN")
      (libsource (lib "eagle-import") (part "RESISTOR_0402"))
    )
    (comp (ref "R54")
      (value "3k")
      (footprint "eagle-import:RESC1005X40AN")
      (libsource (lib "eagle-import") (part "RESISTOR_0402"))
    )
    (comp (ref "R55")
      (value "3k")
      (footprint "eagle-import:RESC1005X40AN")
      (libsource (lib "eagle-import") (part "RESISTOR_0402"))
    )
    (comp (ref "R56")
      (value "2k")
      (footprint "eagle-import:RESC1005X40AN")
      (libsource (lib "eagle-import") (part "RESISTOR_0402"))
    )
    (comp (ref "R57")
      (value "2k")
      (footprint "eagle-import:RESC1005X40AN")
      (libsource (lib "eagle-import") (part "RESISTOR_0402"))
    )
    (comp (ref "R58")
      (value "2k")
      (footprint "eagle-import:RESC1005X40AN")
      (libsource (lib "eagle-import") (part "RESISTOR_0402"))
    )
    (comp (ref "R59")
      (value "2k")
      (footprint "eagle-import:RESC1005X40AN")
      (libsource (lib "eagle-import") (part "RESISTOR_0402"))
    )
    (comp (ref "R60")
      (value "2k")
      (footprint "eagle-import:RESC1005X40AN")
      (libsource (lib "eagle-import") (part "RESISTOR_0402"))
    )
    (comp (ref "R61")
      (value "2k")
      (footprint "eagle-import:RESC1005X40AN")
      (libsource (lib "eagle-import") (part "RESISTOR_0402"))
    )
    (comp (ref "R62")
      (value "2k")
      (footprint "eagle-import:RESC1005X40AN")
      (libsource (lib "eagle-import") (part "RESISTOR_0402"))
    )
    (comp (ref "R63")
      (value "2k")
      (footprint "eagle-import:RESC1005X40AN")
      (libsource (lib "eagle-import") (part "RESISTOR_0402"))
    )
    (comp (ref "R64")
      (value "10k")
      (footprint "eagle-import:RESC1005X40AN")
      (libsource (lib "eagle-import") (part "RESISTOR_0402"))
    )
    (comp (ref "R65")
      (value "10k")
      (footprint "eagle-import:RESC1005X40AN")
      (libsource (lib "eagle-import") (part "RESISTOR_0402"))
    )
    (comp (ref "R66")
      (value "10R")
      (footprint "eagle-import:RESC1608X55N")
      (libsource (lib "eagle-import") (part "RESISTOR_0603"))
    )
    (comp (ref "R67")
      (value "10k")
      (footprint "eagle-import:RESC1005X40AN")
      (libsource (lib "eagle-import") (part "RESISTOR_0402"))
    )
    (comp (ref "R68")
      (value "10k")
      (footprint "eagle-import:RESC1005X40AN")
      (libsource (lib "eagle-import") (part "RESISTOR_0402"))
    )
    (comp (ref "R69")
      (value "10k")
      (footprint "eagle-import:RESC1005X40AN")
      (libsource (lib "eagle-import") (part "RESISTOR_0402"))
    )
    (comp (ref "R70")
      (value "10k")
      (footprint "eagle-import:RESC1005X40AN")
      (libsource (lib "eagle-import") (part "RESISTOR_0402"))
    )
    (comp (ref "R71")
      (value "10k")
      (footprint "eagle-import:RESC1005X40AN")
      (libsource (lib "eagle-import") (part "RESISTOR_0402"))
    )
    (comp (ref "R72")
      (value "1k")
      (footprint "eagle-import:RESC1005X40AN")
      (libsource (lib "eagle-import") (part "RESISTOR_0402"))
    )
    (comp (ref "R73")
      (value "1k")
      (footprint "eagle-import:RESC1005X40AN")
      (libsource (lib "eagle-import") (part "RESISTOR_0402"))
    )
    (comp (ref "R74")
      (value "1k")
      (footprint "eagle-import:RESC1005X40AN")
      (libsource (lib "eagle-import") (part "RESISTOR_0402"))
    )
    (comp (ref "R75")
      (value "1k")
      (footprint "eagle-import:RESC1005X40AN")
      (libsource (lib "eagle-import") (part "RESISTOR_0402"))
    )
    (comp (ref "R76")
      (value "1k")
      (footprint "eagle-import:RESC1005X40AN")
      (libsource (lib "eagle-import") (part "RESISTOR_0402"))
    )
    (comp (ref "R77")
      (value "1k")
      (footprint "eagle-import:RESC1005X40AN")
      (libsource (lib "eagle-import") (part "RESISTOR_0402"))
    )
    (comp (ref "R78")
      (value "1k")
      (footprint "eagle-import:RESC1005X40AN")
      (libsource (lib "eagle-import") (part "RESISTOR_0402"))
    )
    (comp (ref "R79")
      (value "2.2E")
      (footprint "eagle-import:RESC1608X55N")
      (libsource (lib "eagle-import") (part "RESISTOR_0603"))
    )
    (comp (ref "R81")
      (value "LRMAP3920SUNT")
      (footprint "eagle-import:SMD4")
      (libsource (lib "eagle-import") (part "LRMAP3920SUNT"))
    )
    (comp (ref "R82")
      (value "1.6k")
      (footprint "eagle-import:RESC1608X55N")
      (libsource (lib "eagle-import") (part "RESISTOR_0603"))
    )
    (comp (ref "R83")
      (value "16.2k")
      (footprint "eagle-import:RESC1608X55N")
      (libsource (lib "eagle-import") (part "RESISTOR_0603"))
    )
    (comp (ref "R84")
      (value "LRMAP3920SUNT")
      (footprint "eagle-import:SMD4")
      (libsource (lib "eagle-import") (part "LRMAP3920SUNT"))
    )
    (comp (ref "R85")
      (value "10k")
      (footprint "eagle-import:RESC1608X55N")
      (libsource (lib "eagle-import") (part "RESISTOR_0603"))
    )
    (comp (ref "R86")
      (value "526E")
      (footprint "eagle-import:RESC1608X55N")
      (libsource (lib "eagle-import") (part "RESISTOR_0603"))
    )
    (comp (ref "R87")
      (value "127E")
      (footprint "eagle-import:RESC1608X55N")
      (libsource (lib "eagle-import") (part "RESISTOR_0603"))
    )
    (comp (ref "R88")
      (value "127E")
      (footprint "eagle-import:RESC1608X55N")
      (libsource (lib "eagle-import") (part "RESISTOR_0603"))
    )
    (comp (ref "R89")
      (value "100k")
      (footprint "eagle-import:RESC1608X55N")
      (libsource (lib "eagle-import") (part "RESISTOR_0603"))
    )
    (comp (ref "R90")
      (value "200k")
      (footprint "eagle-import:RESC1608X55N")
      (libsource (lib "eagle-import") (part "RESISTOR_0603"))
    )
    (comp (ref "R91")
      (value "1R")
      (footprint "eagle-import:RESC1608X55N")
      (libsource (lib "eagle-import") (part "RESISTOR_0603"))
    )
    (comp (ref "R107")
      (value "100k")
      (footprint "eagle-import:RESC1608X55N")
      (libsource (lib "eagle-import") (part "RESISTOR_0603"))
    )
    (comp (ref "R108")
      (value "0R")
      (footprint "eagle-import:RESC1005X40AN")
      (libsource (lib "eagle-import") (part "RESISTOR_0402"))
    )
    (comp (ref "R118")
      (value "0E")
      (footprint "eagle-import:RESC1005X40AN")
      (libsource (lib "eagle-import") (part "RESISTOR_0402"))
    )
    (comp (ref "R122")
      (value "0E")
      (footprint "eagle-import:RESC1005X40AN")
      (libsource (lib "eagle-import") (part "RESISTOR_0402"))
    )
    (comp (ref "R123")
      (value "0E")
      (footprint "eagle-import:RESC1005X40AN")
      (libsource (lib "eagle-import") (part "RESISTOR_0402"))
    )
    (comp (ref "R124")
      (value "0E")
      (footprint "eagle-import:RESC1005X40AN")
      (libsource (lib "eagle-import") (part "RESISTOR_0402"))
    )
    (comp (ref "TP2")
      (value "TPTH7035")
      (footprint "eagle-import:TP7035")
      (libsource (lib "eagle-import") (part "TPTH7035"))
    )
    (comp (ref "TP3")
      (value "TPTH7035")
      (footprint "eagle-import:TP7035")
      (libsource (lib "eagle-import") (part "TPTH7035"))
    )
    (comp (ref "TP4")
      (value "TPTH7035")
      (footprint "eagle-import:TP7035")
      (libsource (lib "eagle-import") (part "TPTH7035"))
    )
    (comp (ref "TP5")
      (value "TPTH7035")
      (footprint "eagle-import:TP7035")
      (libsource (lib "eagle-import") (part "TPTH7035"))
    )
    (comp (ref "TP6")
      (value "TPTH7035")
      (footprint "eagle-import:TP7035")
      (libsource (lib "eagle-import") (part "TPTH7035"))
    )
    (comp (ref "TP7")
      (value "TPTH7035")
      (footprint "eagle-import:TP7035")
      (libsource (lib "eagle-import") (part "TPTH7035"))
    )
    (comp (ref "TP8")
      (value "TPTH7035")
      (footprint "eagle-import:TP7035")
      (libsource (lib "eagle-import") (part "TPTH7035"))
    )
    (comp (ref "TP9")
      (value "TPTH7035")
      (footprint "eagle-import:TP7035")
      (libsource (lib "eagle-import") (part "TPTH7035"))
    )
    (comp (ref "C1")
      (value "0.047uF")
      (footprint "eagle-import:CAPC1608X92N")
      (libsource (lib "eagle-import") (part "CAPACITOR_0603"))
    )
    (comp (ref "C2")
      (value "0.047uF")
      (footprint "eagle-import:CAPC1608X92N")
      (libsource (lib "eagle-import") (part "CAPACITOR_0603"))
    )
    (comp (ref "C3")
      (value "0.047uF")
      (footprint "eagle-import:CAPC1608X92N")
      (libsource (lib "eagle-import") (part "CAPACITOR_0603"))
    )
    (comp (ref "C4")
      (value "0.047uF")
      (footprint "eagle-import:CAPC1608X92N")
      (libsource (lib "eagle-import") (part "CAPACITOR_0603"))
    )
    (comp (ref "C5")
      (value "0.047uF")
      (footprint "eagle-import:CAPC1608X92N")
      (libsource (lib "eagle-import") (part "CAPACITOR_0603"))
    )
    (comp (ref "C6")
      (value "0.047uF")
      (footprint "eagle-import:CAPC1608X92N")
      (libsource (lib "eagle-import") (part "CAPACITOR_0603"))
    )
    (comp (ref "C7")
      (value "0.047uF")
      (footprint "eagle-import:CAPC1608X92N")
      (libsource (lib "eagle-import") (part "CAPACITOR_0603"))
    )
    (comp (ref "C8")
      (value "0.47uF")
      (footprint "eagle-import:CAPC3215X168N")
      (libsource (lib "eagle-import") (part "CAPACITOR_1206"))
    )
    (comp (ref "C9")
      (value "0.47uF")
      (footprint "eagle-import:CAPC3215X168N")
      (libsource (lib "eagle-import") (part "CAPACITOR_1206"))
    )
    (comp (ref "C10")
      (value "0.47uF")
      (footprint "eagle-import:CAPC3215X168N")
      (libsource (lib "eagle-import") (part "CAPACITOR_1206"))
    )
    (comp (ref "C11")
      (value "0.47uF")
      (footprint "eagle-import:CAPC3215X168N")
      (libsource (lib "eagle-import") (part "CAPACITOR_1206"))
    )
    (comp (ref "C12")
      (value "0.47uF")
      (footprint "eagle-import:CAPC3215X168N")
      (libsource (lib "eagle-import") (part "CAPACITOR_1206"))
    )
    (comp (ref "C13")
      (value "0.47uF")
      (footprint "eagle-import:CAPC3215X168N")
      (libsource (lib "eagle-import") (part "CAPACITOR_1206"))
    )
    (comp (ref "C14")
      (value "0.47uF")
      (footprint "eagle-import:CAPC3215X168N")
      (libsource (lib "eagle-import") (part "CAPACITOR_1206"))
    )
    (comp (ref "C15")
      (value "0.047uF")
      (footprint "eagle-import:CAPC1005X60N")
      (libsource (lib "eagle-import") (part "CAPACITOR_0402"))
    )
    (comp (ref "C16")
      (value "0.047uF")
      (footprint "eagle-import:CAPC1005X60N")
      (libsource (lib "eagle-import") (part "CAPACITOR_0402"))
    )
    (comp (ref "C17")
      (value "0.047uF")
      (footprint "eagle-import:CAPC1005X60N")
      (libsource (lib "eagle-import") (part "CAPACITOR_0402"))
    )
    (comp (ref "C18")
      (value "0.047uF")
      (footprint "eagle-import:CAPC1005X60N")
      (libsource (lib "eagle-import") (part "CAPACITOR_0402"))
    )
    (comp (ref "C19")
      (value "0.047uF")
      (footprint "eagle-import:CAPC1005X60N")
      (libsource (lib "eagle-import") (part "CAPACITOR_0402"))
    )
    (comp (ref "C20")
      (value "0.047uF")
      (footprint "eagle-import:CAPC1005X60N")
      (libsource (lib "eagle-import") (part "CAPACITOR_0402"))
    )
    (comp (ref "C21")
      (value "0.047uF")
      (footprint "eagle-import:CAPC1005X60N")
      (libsource (lib "eagle-import") (part "CAPACITOR_0402"))
    )
    (comp (ref "C22")
      (value "2.2uF")
      (footprint "eagle-import:CAPC1608X92N")
      (libsource (lib "eagle-import") (part "CAPACITOR_0603"))
    )
    (comp (ref "C23")
      (value ".047uF")
      (footprint "eagle-import:CAPC1005X60N")
      (libsource (lib "eagle-import") (part "CAPACITOR_0402"))
    )
    (comp (ref "C79")
      (value "0.1uF")
      (footprint "eagle-import:CAPC1608X92N")
      (libsource (lib "eagle-import") (part "CAPACITOR_0603"))
    )
    (comp (ref "CELL8+")
      (value "GF_BMS_CELL_PADP_PAD")
      (footprint "eagle-import:CELL_PAD")
      (libsource (lib "eagle-import") (part "GF_BMS_CELL_PADP_PAD"))
    )
    (comp (ref "CELL9+")
      (value "GF_BMS_CELL_PADP_PAD")
      (footprint "eagle-import:CELL_PAD")
      (libsource (lib "eagle-import") (part "GF_BMS_CELL_PADP_PAD"))
    )
    (comp (ref "CELL10+")
      (value "GF_BMS_CELL_PADP_PAD")
      (footprint "eagle-import:CELL_PAD")
      (libsource (lib "eagle-import") (part "GF_BMS_CELL_PADP_PAD"))
    )
    (comp (ref "CELL11+")
      (value "GF_BMS_CELL_PADP_PAD")
      (footprint "eagle-import:CELL_PAD")
      (libsource (lib "eagle-import") (part "GF_BMS_CELL_PADP_PAD"))
    )
    (comp (ref "CELL12+")
      (value "GF_BMS_CELL_PADP_PAD")
      (footprint "eagle-import:CELL_PAD")
      (libsource (lib "eagle-import") (part "GF_BMS_CELL_PADP_PAD"))
    )
    (comp (ref "CELL13+")
      (value "GF_BMS_CELL_PADP_PAD")
      (footprint "eagle-import:CELL_PAD")
      (libsource (lib "eagle-import") (part "GF_BMS_CELL_PADP_PAD"))
    )
    (comp (ref "CELL14+")
      (value "GF_BMS_CELL_PADP_PAD")
      (footprint "eagle-import:CELL_PAD")
      (fields (field (name "SPICEPREFIX") "X"))
      (libsource (lib "eagle-import") (part "GF_BMS_CELL_PADP_PAD"))
    )
    (comp (ref "D21")
      (value "8.2V")
      (footprint "eagle-import:SOD3718X135N")
      (libsource (lib "eagle-import") (part "ZENER_SOD-123"))
    )
    (comp (ref "IC1")
      (value "MC33771BEP")
      (footprint "eagle-import:64PIN-LQFP")
      (libsource (lib "eagle-import") (part "MC33771BEP"))
    )
    (comp (ref "IC2")
      (value "SFH6156-1")
      (footprint "eagle-import:SFH")
      (fields (field (name "MF") "VISHAY/TELEFUNKEN") (field (name "MPN") "SFH6156-4T"))
      (libsource (lib "eagle-import") (part "SFH6156"))
    )
    (comp (ref "IC7")
      (value "SFH6156-1")
      (footprint "eagle-import:SFH")
      (fields (field (name "MF") "VISHAY/TELEFUNKEN") (field (name "MPN") "SFH6156-4T"))
      (libsource (lib "eagle-import") (part "SFH6156"))
    )
    (comp (ref "IC8")
      (value "SFH6156-1")
      (footprint "eagle-import:SFH")
      (fields (field (name "MF") "VISHAY/TELEFUNKEN") (field (name "MPN") "SFH6156-4T"))
      (libsource (lib "eagle-import") (part "SFH6156"))
    )
    (comp (ref "JP5")
      (value "PINHD-1X15")
      (footprint "eagle-import:1X15")
      (libsource (lib "eagle-import") (part "PINHD-1X15"))
    )
    (comp (ref "JP7")
      (value "PINHD-1X2")
      (footprint "eagle-import:1X02")
      (libsource (lib "eagle-import") (part "PINHD-1X2"))
    )
    (comp (ref "R1")
      (value "0E")
      (footprint "eagle-import:RESC1005X40AN")
      (libsource (lib "eagle-import") (part "RESISTOR_0402"))
    )
    (comp (ref "R2")
      (value "0E")
      (footprint "eagle-import:RESC1005X40AN")
      (libsource (lib "eagle-import") (part "RESISTOR_0402"))
    )
    (comp (ref "R3")
      (value "0E")
      (footprint "eagle-import:RESC1005X40AN")
      (libsource (lib "eagle-import") (part "RESISTOR_0402"))
    )
    (comp (ref "R4")
      (value "0E")
      (footprint "eagle-import:RESC1005X40AN")
      (libsource (lib "eagle-import") (part "RESISTOR_0402"))
    )
    (comp (ref "R5")
      (value "39E")
      (footprint "eagle-import:RESC3225X70N")
      (libsource (lib "eagle-import") (part "RESISTOR_1210"))
    )
    (comp (ref "R6")
      (value "39E")
      (footprint "eagle-import:RESC3225X70N")
      (libsource (lib "eagle-import") (part "RESISTOR_1210"))
    )
    (comp (ref "R7")
      (value "39E")
      (footprint "eagle-import:RESC3225X70N")
      (libsource (lib "eagle-import") (part "RESISTOR_1210"))
    )
    (comp (ref "R8")
      (value "0E")
      (footprint "eagle-import:RESC1005X40AN")
      (libsource (lib "eagle-import") (part "RESISTOR_0402"))
    )
    (comp (ref "R9")
      (value "0E")
      (footprint "eagle-import:RESC1005X40AN")
      (libsource (lib "eagle-import") (part "RESISTOR_0402"))
    )
    (comp (ref "R10")
      (value "0E")
      (footprint "eagle-import:RESC1005X40AN")
      (libsource (lib "eagle-import") (part "RESISTOR_0402"))
    )
    (comp (ref "R11")
      (value "39E")
      (footprint "eagle-import:RESC3225X70N")
      (libsource (lib "eagle-import") (part "RESISTOR_1210"))
    )
    (comp (ref "R12")
      (value "39E")
      (footprint "eagle-import:RESC3225X70N")
      (libsource (lib "eagle-import") (part "RESISTOR_1210"))
    )
    (comp (ref "R13")
      (value "39E")
      (footprint "eagle-import:RESC3225X70N")
      (libsource (lib "eagle-import") (part "RESISTOR_1210"))
    )
    (comp (ref "R14")
      (value "39E")
      (footprint "eagle-import:RESC3225X70N")
      (libsource (lib "eagle-import") (part "RESISTOR_1210"))
    )
    (comp (ref "R15")
      (value "3k")
      (footprint "eagle-import:RESC1005X40AN")
      (libsource (lib "eagle-import") (part "RESISTOR_0402"))
    )
    (comp (ref "R16")
      (value "3k")
      (footprint "eagle-import:RESC1005X40AN")
      (libsource (lib "eagle-import") (part "RESISTOR_0402"))
    )
    (comp (ref "R17")
      (value "3k")
      (footprint "eagle-import:RESC1005X40AN")
      (libsource (lib "eagle-import") (part "RESISTOR_0402"))
    )
    (comp (ref "R18")
      (value "3k")
      (footprint "eagle-import:RESC1005X40AN")
      (libsource (lib "eagle-import") (part "RESISTOR_0402"))
    )
    (comp (ref "R19")
      (value "3k")
      (footprint "eagle-import:RESC1005X40AN")
      (libsource (lib "eagle-import") (part "RESISTOR_0402"))
    )
    (comp (ref "R20")
      (value "3k")
      (footprint "eagle-import:RESC1005X40AN")
      (libsource (lib "eagle-import") (part "RESISTOR_0402"))
    )
    (comp (ref "R21")
      (value "3k")
      (footprint "eagle-import:RESC1005X40AN")
      (libsource (lib "eagle-import") (part "RESISTOR_0402"))
    )
    (comp (ref "R22")
      (value "2k")
      (footprint "eagle-import:RESC1005X40AN")
      (libsource (lib "eagle-import") (part "RESISTOR_0402"))
    )
    (comp (ref "R23")
      (value "2k")
      (footprint "eagle-import:RESC1005X40AN")
      (libsource (lib "eagle-import") (part "RESISTOR_0402"))
    )
    (comp (ref "R24")
      (value "2k")
      (footprint "eagle-import:RESC1005X40AN")
      (libsource (lib "eagle-import") (part "RESISTOR_0402"))
    )
    (comp (ref "R25")
      (value "2k")
      (footprint "eagle-import:RESC1005X40AN")
      (libsource (lib "eagle-import") (part "RESISTOR_0402"))
    )
    (comp (ref "R26")
      (value "2k")
      (footprint "eagle-import:RESC1005X40AN")
      (libsource (lib "eagle-import") (part "RESISTOR_0402"))
    )
    (comp (ref "R27")
      (value "2k")
      (footprint "eagle-import:RESC1005X40AN")
      (libsource (lib "eagle-import") (part "RESISTOR_0402"))
    )
    (comp (ref "R28")
      (value "2k")
      (footprint "eagle-import:RESC1005X40AN")
      (libsource (lib "eagle-import") (part "RESISTOR_0402"))
    )
    (comp (ref "R29")
      (value "10k")
      (footprint "eagle-import:RESC1005X40AN")
      (libsource (lib "eagle-import") (part "RESISTOR_0402"))
    )
    (comp (ref "R30")
      (value "10k")
      (footprint "eagle-import:RESC1005X40AN")
      (libsource (lib "eagle-import") (part "RESISTOR_0402"))
    )
    (comp (ref "R31")
      (value "127E")
      (footprint "eagle-import:RESC1608X55N")
      (libsource (lib "eagle-import") (part "RESISTOR_0603"))
    )
    (comp (ref "R95")
      (value "127E")
      (footprint "eagle-import:RESC1608X55N")
      (libsource (lib "eagle-import") (part "RESISTOR_0603"))
    )
    (comp (ref "R97")
      (value "127E")
      (footprint "eagle-import:RESC1608X55N")
      (libsource (lib "eagle-import") (part "RESISTOR_0603"))
    )
    (comp (ref "R109")
      (value "10K")
      (footprint "eagle-import:RESC1005X40AN")
      (libsource (lib "eagle-import") (part "RESISTOR_0402"))
    )
    (comp (ref "R110")
      (value "10K")
      (footprint "eagle-import:RESC1005X40AN")
      (libsource (lib "eagle-import") (part "RESISTOR_0402"))
    )
    (comp (ref "R119")
      (value "127E")
      (footprint "eagle-import:RESC1608X55N")
      (libsource (lib "eagle-import") (part "RESISTOR_0603"))
    )
  )
  (nets
    (net (code "1") (name "+12V") (class "Default")
      (node (ref "C70") (pin "2") (pinfunction "2_2") (pintype "passive"))
      (node (ref "C82") (pin "2") (pinfunction "2_2") (pintype "passive"))
      (node (ref "C83") (pin "1") (pinfunction "1_1") (pintype "passive"))
      (node (ref "C84") (pin "1") (pinfunction "1_1") (pintype "passive"))
      (node (ref "C85") (pin "1") (pinfunction "1_1") (pintype "passive"))
      (node (ref "C87") (pin "2") (pinfunction "2_2") (pintype "passive"))
      (node (ref "C88") (pin "1") (pinfunction "1_1") (pintype "passive"))
      (node (ref "C91") (pin "+") (pinfunction "+_+") (pintype "passive"))
      (node (ref "IC10") (pin "6") (pinfunction "VCC_6") (pintype "power_in"))
      (node (ref "IC11") (pin "6") (pinfunction "VCC_6") (pintype "power_in"))
      (node (ref "IC9") (pin "6") (pinfunction "VCC_6") (pintype "power_in"))
      (node (ref "L1") (pin "2") (pinfunction "2_2") (pintype "power_in"))
      (node (ref "LED1") (pin "2") (pinfunction "A_2") (pintype "passive"))
      (node (ref "LED2") (pin "2") (pinfunction "A_2") (pintype "passive"))
      (node (ref "LED3") (pin "A") (pinfunction "A_A") (pintype "passive"))
      (node (ref "LED4") (pin "A") (pinfunction "A_A") (pintype "passive"))
      (node (ref "R85") (pin "1") (pinfunction "1_1") (pintype "passive"))
      (node (ref "U1") (pin "3") (pinfunction "IN_3") (pintype "bidirectional"))
      (node (ref "U2") (pin "3") (pinfunction "IN_3") (pintype "bidirectional"))
    )
    (net (code "2") (name "3.3V") (class "Default")
      (node (ref "+3.3V") (pin "P$1") (pinfunction "P$1_P$1") (pintype "passive"))
      (node (ref "C69") (pin "2") (pinfunction "2_2") (pintype "passive"))
      (node (ref "JP3") (pin "3") (pinfunction "3_3") (pintype "passive"))
      (node (ref "JP4") (pin "13") (pinfunction "13_13") (pintype "passive"))
      (node (ref "JP4") (pin "7") (pinfunction "7_7") (pintype "passive"))
      (node (ref "R109") (pin "2") (pinfunction "2_2") (pintype "passive"))
      (node (ref "R110") (pin "2") (pinfunction "2_2") (pintype "passive"))
      (node (ref "U1") (pin "2") (pinfunction "OUT_2") (pintype "bidirectional"))
    )
    (net (code "3") (name "5V") (class "Default")
      (node (ref "+5V") (pin "P$1") (pinfunction "P$1_P$1") (pintype "passive"))
      (node (ref "C81") (pin "2") (pinfunction "2_2") (pintype "passive"))
      (node (ref "JP6") (pin "10") (pinfunction "10_10") (pintype "passive"))
      (node (ref "JP6") (pin "11") (pinfunction "11_11") (pintype "passive"))
      (node (ref "U2") (pin "2") (pinfunction "OUT_2") (pintype "bidirectional"))
    )
    (net (code "4") (name "BGND") (class "Default")
      (node (ref "BGND") (pin "1") (pinfunction "P$1_1") (pintype "passive"))
      (node (ref "CELL1-") (pin "P$1") (pinfunction "S_P$1") (pintype "power_in"))
      (node (ref "R122") (pin "1") (pinfunction "1_1") (pintype "passive"))
      (node (ref "R123") (pin "1") (pinfunction "1_1") (pintype "passive"))
      (node (ref "R124") (pin "1") (pinfunction "1_1") (pintype "passive"))
      (node (ref "R34") (pin "1") (pinfunction "1_1") (pintype "passive"))
      (node (ref "R38") (pin "1") (pinfunction "1_1") (pintype "passive"))
      (node (ref "R81") (pin "4") (pinfunction "4_4") (pintype "passive"))
      (node (ref "R81") (pin "6") (pinfunction "4_6") (pintype "passive"))
      (node (ref "R84") (pin "4") (pinfunction "4_4") (pintype "passive"))
      (node (ref "R84") (pin "6") (pinfunction "4_6") (pintype "passive"))
      (node (ref "R98") (pin "1") (pinfunction "1_1") (pintype "passive"))
    )
    (net (code "5") (name "BST") (class "Default")
      (node (ref "C65") (pin "1") (pinfunction "1_1") (pintype "passive"))
      (node (ref "IC3") (pin "4") (pinfunction "BST_4") (pintype "output"))
    )
    (net (code "6") (name "CANH") (class "Default")
      (node (ref "CH") (pin "P$1") (pinfunction "P$1_P$1") (pintype "passive"))
      (node (ref "D15") (pin "K") (pinfunction "K_K") (pintype "passive"))
      (node (ref "JP6") (pin "15") (pinfunction "15_15") (pintype "passive"))
    )
    (net (code "7") (name "CANL") (class "Default")
      (node (ref "CL") (pin "P$1") (pinfunction "P$1_P$1") (pintype "passive"))
      (node (ref "D14") (pin "K") (pinfunction "K_K") (pintype "passive"))
      (node (ref "JP6") (pin "14") (pinfunction "14_14") (pintype "passive"))
    )
    (net (code "8") (name "CB_1") (class "Default")
      (node (ref "IC1") (pin "36") (pinfunction "CB_1_36") (pintype "output"))
      (node (ref "R49") (pin "2") (pinfunction "2_2") (pintype "passive"))
    )
    (net (code "9") (name "CB_2") (class "Default")
      (node (ref "IC1") (pin "34") (pinfunction "CB_2_34") (pintype "output"))
      (node (ref "R48") (pin "2") (pinfunction "2_2") (pintype "passive"))
    )
    (net (code "10") (name "CB_2{slash}1_C") (class "Default")
      (node (ref "C31") (pin "1") (pinfunction "1_1") (pintype "passive"))
      (node (ref "IC1") (pin "35") (pinfunction "CB_2:1_C_35") (pintype "output"))
      (node (ref "JP5") (pin "7") (pinfunction "7_7") (pintype "passive"))
      (node (ref "R41") (pin "2") (pinfunction "2_2") (pintype "passive"))
      (node (ref "R54") (pin "1") (pinfunction "1_1") (pintype "passive"))
    )
    (net (code "11") (name "CB_3") (class "Default")
      (node (ref "IC1") (pin "31") (pinfunction "CB_3_31") (pintype "output"))
      (node (ref "R40") (pin "2") (pinfunction "2_2") (pintype "passive"))
    )
    (net (code "12") (name "CB_3{slash}2_C") (class "Default")
      (node (ref "C28") (pin "1") (pinfunction "1_1") (pintype "passive"))
      (node (ref "JP5") (pin "15") (pinfunction "15_15") (pintype "passive"))
      (node (ref "R37") (pin "2") (pinfunction "2_2") (pintype "passive"))
      (node (ref "R40") (pin "1") (pinfunction "1_1") (pintype "passive"))
      (node (ref "R48") (pin "1") (pinfunction "1_1") (pintype "passive"))
      (node (ref "R55") (pin "1") (pinfunction "1_1") (pintype "passive"))
    )
    (net (code "13") (name "CB_4") (class "Default")
      (node (ref "IC1") (pin "29") (pinfunction "CB_4_29") (pintype "output"))
      (node (ref "R47") (pin "2") (pinfunction "2_2") (pintype "passive"))
    )
    (net (code "14") (name "CB_4{slash}3_C") (class "Default")
      (node (ref "C30") (pin "1") (pinfunction "1_1") (pintype "passive"))
      (node (ref "IC1") (pin "30") (pinfunction "CB_4:3_C_30") (pintype "output"))
      (node (ref "JP5") (pin "1") (pinfunction "1_1") (pintype "passive"))
      (node (ref "R43") (pin "2") (pinfunction "2_2") (pintype "passive"))
      (node (ref "R53") (pin "1") (pinfunction "1_1") (pintype "passive"))
    )
    (net (code "15") (name "CB_5") (class "Default")
      (node (ref "IC1") (pin "26") (pinfunction "CB_5_26") (pintype "output"))
      (node (ref "R35") (pin "2") (pinfunction "2_2") (pintype "passive"))
    )
    (net (code "16") (name "CB_5{slash}4_C") (class "Default")
      (node (ref "C24") (pin "1") (pinfunction "1_1") (pintype "passive"))
      (node (ref "JP5") (pin "14") (pinfunction "14_14") (pintype "passive"))
      (node (ref "R32") (pin "2") (pinfunction "2_2") (pintype "passive"))
      (node (ref "R35") (pin "1") (pinfunction "1_1") (pintype "passive"))
      (node (ref "R47") (pin "1") (pinfunction "1_1") (pintype "passive"))
      (node (ref "R52") (pin "1") (pinfunction "1_1") (pintype "passive"))
    )
    (net (code "17") (name "CB_6") (class "Default")
      (node (ref "IC1") (pin "24") (pinfunction "CB_6_24") (pintype "output"))
      (node (ref "R46") (pin "2") (pinfunction "2_2") (pintype "passive"))
    )
    (net (code "18") (name "CB_6{slash}5_C") (class "Default")
      (node (ref "C25") (pin "1") (pinfunction "1_1") (pintype "passive"))
      (node (ref "IC1") (pin "25") (pinfunction "CB_6:5_C_25") (pintype "output"))
      (node (ref "JP5") (pin "2") (pinfunction "2_2") (pintype "passive"))
      (node (ref "R33") (pin "2") (pinfunction "2_2") (pintype "passive"))
      (node (ref "R44") (pin "1") (pinfunction "1_1") (pintype "passive"))
    )
    (net (code "19") (name "CB_7") (class "Default")
      (node (ref "IC1") (pin "21") (pinfunction "CB_7_21") (pintype "output"))
      (node (ref "R39") (pin "2") (pinfunction "2_2") (pintype "passive"))
    )
    (net (code "20") (name "CB_7{slash}6_C") (class "Default")
      (node (ref "C26") (pin "1") (pinfunction "1_1") (pintype "passive"))
      (node (ref "JP5") (pin "13") (pinfunction "13_13") (pintype "passive"))
      (node (ref "R36") (pin "2") (pinfunction "2_2") (pintype "passive"))
      (node (ref "R39") (pin "1") (pinfunction "1_1") (pintype "passive"))
      (node (ref "R46") (pin "1") (pinfunction "1_1") (pintype "passive"))
      (node (ref "R51") (pin "1") (pinfunction "1_1") (pintype "passive"))
    )
    (net (code "21") (name "CB_8") (class "Default")
      (node (ref "IC1") (pin "19") (pinfunction "CB_8_19") (pintype "output"))
      (node (ref "R12") (pin "2") (pinfunction "2_2") (pintype "passive"))
    )
    (net (code "22") (name "CB_8{slash}7_C") (class "Default")
      (node (ref "C29") (pin "1") (pinfunction "1_1") (pintype "passive"))
      (node (ref "D1") (pin "A") (pinfunction "A_A") (pintype "passive"))
      (node (ref "IC1") (pin "20") (pinfunction "CB_8:7_C_20") (pintype "output"))
      (node (ref "JP5") (pin "3") (pinfunction "3_3") (pintype "passive"))
      (node (ref "R42") (pin "2") (pinfunction "2_2") (pintype "passive"))
      (node (ref "R50") (pin "1") (pinfunction "1_1") (pintype "passive"))
    )
    (net (code "23") (name "CB_9") (class "Default")
      (node (ref "IC1") (pin "16") (pinfunction "CB_9_16") (pintype "output"))
      (node (ref "R5") (pin "2") (pinfunction "2_2") (pintype "passive"))
    )
    (net (code "24") (name "CB_9{slash}8_C") (class "Default")
      (node (ref "C2") (pin "1") (pinfunction "1_1") (pintype "passive"))
      (node (ref "JP5") (pin "12") (pinfunction "12_12") (pintype "passive"))
      (node (ref "R12") (pin "1") (pinfunction "1_1") (pintype "passive"))
      (node (ref "R18") (pin "1") (pinfunction "1_1") (pintype "passive"))
      (node (ref "R2") (pin "2") (pinfunction "2_2") (pintype "passive"))
      (node (ref "R5") (pin "1") (pinfunction "1_1") (pintype "passive"))
    )
    (net (code "25") (name "CB_10") (class "Default")
      (node (ref "IC1") (pin "14") (pinfunction "CB_10_14") (pintype "input"))
      (node (ref "R14") (pin "2") (pinfunction "2_2") (pintype "passive"))
    )
    (net (code "26") (name "CB_10{slash}9_C") (class "Default")
      (node (ref "C7") (pin "1") (pinfunction "1_1") (pintype "passive"))
      (node (ref "D2") (pin "A") (pinfunction "A_A") (pintype "passive"))
      (node (ref "IC1") (pin "15") (pinfunction "CB_10:9_C_15") (pintype "output"))
      (node (ref "JP5") (pin "4") (pinfunction "4_4") (pintype "passive"))
      (node (ref "R10") (pin "1") (pinfunction "1_1") (pintype "passive"))
      (node (ref "R17") (pin "1") (pinfunction "1_1") (pintype "passive"))
    )
    (net (code "27") (name "CB_11") (class "Default")
      (node (ref "IC1") (pin "11") (pinfunction "CB_11_11") (pintype "output"))
      (node (ref "R6") (pin "2") (pinfunction "2_2") (pintype "passive"))
    )
    (net (code "28") (name "CB_11{slash}10_C") (class "Default")
      (node (ref "C4") (pin "1") (pinfunction "1_1") (pintype "passive"))
      (node (ref "JP5") (pin "11") (pinfunction "11_11") (pintype "passive"))
      (node (ref "R14") (pin "1") (pinfunction "1_1") (pintype "passive"))
      (node (ref "R21") (pin "1") (pinfunction "1_1") (pintype "passive"))
      (node (ref "R4") (pin "2") (pinfunction "2_2") (pintype "passive"))
      (node (ref "R6") (pin "1") (pinfunction "1_1") (pintype "passive"))
    )
    (net (code "29") (name "CB_12") (class "Default")
      (node (ref "D4") (pin "A") (pinfunction "A_A") (pintype "passive"))
      (node (ref "IC1") (pin "9") (pinfunction "CB_12_9") (pintype "output"))
      (node (ref "R11") (pin "2") (pinfunction "2_2") (pintype "passive"))
    )
    (net (code "30") (name "CB_12{slash}11_C") (class "Default")
      (node (ref "C6") (pin "1") (pinfunction "1_1") (pintype "passive"))
      (node (ref "IC1") (pin "10") (pinfunction "CB_12:11_C_10") (pintype "output"))
      (node (ref "JP5") (pin "5") (pinfunction "5_5") (pintype "passive"))
      (node (ref "R16") (pin "1") (pinfunction "1_1") (pintype "passive"))
      (node (ref "R9") (pin "2") (pinfunction "2_2") (pintype "passive"))
    )
    (net (code "31") (name "CB_13") (class "Default")
      (node (ref "IC1") (pin "6") (pinfunction "CB_13_6") (pintype "output"))
      (node (ref "R7") (pin "2") (pinfunction "2_2") (pintype "passive"))
    )
    (net (code "32") (name "CB_13{slash}12_C") (class "Default")
      (node (ref "C1") (pin "1") (pinfunction "1_1") (pintype "passive"))
      (node (ref "JP5") (pin "10") (pinfunction "10_10") (pintype "passive"))
      (node (ref "R1") (pin "2") (pinfunction "2_2") (pintype "passive"))
      (node (ref "R11") (pin "1") (pinfunction "1_1") (pintype "passive"))
      (node (ref "R20") (pin "1") (pinfunction "1_1") (pintype "passive"))
      (node (ref "R7") (pin "1") (pinfunction "1_1") (pintype "passive"))
    )
    (net (code "33") (name "CB_14") (class "Default")
      (node (ref "D3") (pin "A") (pinfunction "A_A") (pintype "passive"))
      (node (ref "IC1") (pin "4") (pinfunction "CB_14_4") (pintype "output"))
      (node (ref "R13") (pin "1") (pinfunction "1_1") (pintype "passive"))
    )
    (net (code "34") (name "CB_14+{slash}14_C") (class "Default")
      (node (ref "C3") (pin "1") (pinfunction "1_1") (pintype "passive"))
      (node (ref "JP5") (pin "9") (pinfunction "9_9") (pintype "passive"))
      (node (ref "R119") (pin "1") (pinfunction "1_1") (pintype "passive"))
      (node (ref "R13") (pin "2") (pinfunction "2_2") (pintype "passive"))
      (node (ref "R19") (pin "1") (pinfunction "1_1") (pintype "passive"))
      (node (ref "R3") (pin "2") (pinfunction "2_2") (pintype "passive"))
      (node (ref "R66") (pin "1") (pinfunction "1_1") (pintype "passive"))
    )
    (net (code "35") (name "CB_14{slash}13_C") (class "Default")
      (node (ref "C5") (pin "1") (pinfunction "1_1") (pintype "passive"))
      (node (ref "IC1") (pin "5") (pinfunction "CB_14:13C_5") (pintype "output"))
      (node (ref "JP5") (pin "6") (pinfunction "6_6") (pintype "passive"))
      (node (ref "R15") (pin "1") (pinfunction "1_1") (pintype "passive"))
      (node (ref "R8") (pin "2") (pinfunction "2_2") (pintype "passive"))
    )
    (net (code "36") (name "CELL1-") (class "Default")
      (node (ref "C27") (pin "1") (pinfunction "1_1") (pintype "passive"))
      (node (ref "JP5") (pin "8") (pinfunction "8_8") (pintype "passive"))
      (node (ref "R38") (pin "2") (pinfunction "2_2") (pintype "passive"))
      (node (ref "R45") (pin "1") (pinfunction "1_1") (pintype "passive"))
      (node (ref "R49") (pin "1") (pinfunction "1_1") (pintype "passive"))
    )
    (net (code "37") (name "CELL14+") (class "Default")
      (node (ref "C63") (pin "2") (pinfunction "2_2") (pintype "passive"))
      (node (ref "C64") (pin "2") (pinfunction "2_2") (pintype "passive"))
      (node (ref "C90") (pin "+") (pinfunction "+_+") (pintype "passive"))
      (node (ref "CELL14+") (pin "P$1") (pinfunction "S_P$1") (pintype "power_in"))
      (node (ref "IC3") (pin "10") (pinfunction "VIN_10") (pintype "input"))
      (node (ref "IC3") (pin "11") (pinfunction "VIN_11") (pintype "input"))
      (node (ref "IC3") (pin "5") (pinfunction "VIN_5") (pintype "input"))
      (node (ref "IC3") (pin "6") (pinfunction "VIN_6") (pintype "input"))
      (node (ref "IC3") (pin "7") (pinfunction "VIN_7") (pintype "input"))
      (node (ref "IC3") (pin "8") (pinfunction "VIN_8") (pintype "input"))
      (node (ref "IC3") (pin "9") (pinfunction "VIN_9") (pintype "input"))
      (node (ref "R3") (pin "1") (pinfunction "1_1") (pintype "passive"))
      (node (ref "R79") (pin "1") (pinfunction "1_1") (pintype "passive"))
    )
    (net (code "38") (name "CHG_FET") (class "Default")
      (node (ref "IC10") (pin "5") (pinfunction "VO_5") (pintype "power_in"))
      (node (ref "Q1") (pin "2") (pinfunction "S_2") (pintype "power_in"))
    )
    (net (code "39") (name "CHG_GATE") (class "Default")
      (node (ref "JP4") (pin "9") (pinfunction "9_9") (pintype "passive"))
      (node (ref "R96") (pin "1") (pinfunction "1_1") (pintype "passive"))
    )
    (net (code "40") (name "CSB") (class "Default")
      (node (ref "IC1") (pin "41") (pinfunction "CSB_41") (pintype "input"))
      (node (ref "JP6") (pin "4") (pinfunction "4_4") (pintype "passive"))
    )
    (net (code "41") (name "CT_1") (class "Default")
      (node (ref "C45") (pin "2") (pinfunction "2_2") (pintype "passive"))
      (node (ref "C46") (pin "1") (pinfunction "1_1") (pintype "passive"))
      (node (ref "IC1") (pin "37") (pinfunction "CT_1_37") (pintype "input"))
      (node (ref "R62") (pin "2") (pinfunction "2_2") (pintype "passive"))
    )
    (net (code "42") (name "CT_2") (class "Default")
      (node (ref "C44") (pin "2") (pinfunction "2_2") (pintype "passive"))
      (node (ref "C45") (pin "1") (pinfunction "1_1") (pintype "passive"))
      (node (ref "IC1") (pin "33") (pinfunction "CT_2_33") (pintype "input"))
      (node (ref "R61") (pin "2") (pinfunction "2_2") (pintype "passive"))
    )
    (net (code "43") (name "CT_3") (class "Default")
      (node (ref "C43") (pin "2") (pinfunction "2_2") (pintype "passive"))
      (node (ref "C44") (pin "1") (pinfunction "1_1") (pintype "passive"))
      (node (ref "IC1") (pin "32") (pinfunction "CT_3_32") (pintype "input"))
      (node (ref "R60") (pin "2") (pinfunction "2_2") (pintype "passive"))
    )
    (net (code "44") (name "CT_4") (class "Default")
      (node (ref "C42") (pin "2") (pinfunction "2_2") (pintype "passive"))
      (node (ref "C43") (pin "1") (pinfunction "1_1") (pintype "passive"))
      (node (ref "IC1") (pin "28") (pinfunction "CT_4_28") (pintype "input"))
      (node (ref "R59") (pin "2") (pinfunction "2_2") (pintype "passive"))
    )
    (net (code "45") (name "CT_5") (class "Default")
      (node (ref "C41") (pin "2") (pinfunction "2_2") (pintype "passive"))
      (node (ref "C42") (pin "1") (pinfunction "1_1") (pintype "passive"))
      (node (ref "IC1") (pin "27") (pinfunction "CT_5_27") (pintype "input"))
      (node (ref "R58") (pin "2") (pinfunction "2_2") (pintype "passive"))
    )
    (net (code "46") (name "CT_6") (class "Default")
      (node (ref "C40") (pin "2") (pinfunction "2_2") (pintype "passive"))
      (node (ref "C41") (pin "1") (pinfunction "1_1") (pintype "passive"))
      (node (ref "IC1") (pin "23") (pinfunction "CT_6_23") (pintype "input"))
      (node (ref "R57") (pin "2") (pinfunction "2_2") (pintype "passive"))
    )
    (net (code "47") (name "CT_7") (class "Default")
      (node (ref "C21") (pin "2") (pinfunction "2_2") (pintype "passive"))
      (node (ref "C40") (pin "1") (pinfunction "1_1") (pintype "passive"))
      (node (ref "IC1") (pin "22") (pinfunction "CT_7_22") (pintype "input"))
      (node (ref "R56") (pin "2") (pinfunction "2_2") (pintype "passive"))
    )
    (net (code "48") (name "CT_8") (class "Default")
      (node (ref "C20") (pin "2") (pinfunction "2_2") (pintype "passive"))
      (node (ref "C21") (pin "1") (pinfunction "1_1") (pintype "passive"))
      (node (ref "IC1") (pin "18") (pinfunction "CT_8_18") (pintype "input"))
      (node (ref "R28") (pin "2") (pinfunction "2_2") (pintype "passive"))
    )
    (net (code "49") (name "CT_9") (class "Default")
      (node (ref "C19") (pin "2") (pinfunction "2_2") (pintype "passive"))
      (node (ref "C20") (pin "1") (pinfunction "1_1") (pintype "passive"))
      (node (ref "IC1") (pin "17") (pinfunction "CT_9_17") (pintype "input"))
      (node (ref "R27") (pin "2") (pinfunction "2_2") (pintype "passive"))
    )
    (net (code "50") (name "CT_10") (class "Default")
      (node (ref "C18") (pin "2") (pinfunction "2_2") (pintype "passive"))
      (node (ref "C19") (pin "1") (pinfunction "1_1") (pintype "passive"))
      (node (ref "IC1") (pin "13") (pinfunction "CT_10_13") (pintype "input"))
      (node (ref "R26") (pin "2") (pinfunction "2_2") (pintype "passive"))
    )
    (net (code "51") (name "CT_11") (class "Default")
      (node (ref "C17") (pin "2") (pinfunction "2_2") (pintype "passive"))
      (node (ref "C18") (pin "1") (pinfunction "1_1") (pintype "passive"))
      (node (ref "IC1") (pin "12") (pinfunction "CT_11_12") (pintype "input"))
      (node (ref "R25") (pin "2") (pinfunction "2_2") (pintype "passive"))
    )
    (net (code "52") (name "CT_12") (class "Default")
      (node (ref "C16") (pin "2") (pinfunction "2_2") (pintype "passive"))
      (node (ref "C17") (pin "1") (pinfunction "1_1") (pintype "passive"))
      (node (ref "IC1") (pin "8") (pinfunction "CT_12_8") (pintype "input"))
      (node (ref "R24") (pin "2") (pinfunction "2_2") (pintype "passive"))
    )
    (net (code "53") (name "CT_13") (class "Default")
      (node (ref "C15") (pin "2") (pinfunction "2_2") (pintype "passive"))
      (node (ref "C16") (pin "1") (pinfunction "1_1") (pintype "passive"))
      (node (ref "IC1") (pin "7") (pinfunction "CT_13_7") (pintype "input"))
      (node (ref "R23") (pin "2") (pinfunction "2_2") (pintype "passive"))
    )
    (net (code "54") (name "CT_14") (class "Default")
      (node (ref "C15") (pin "1") (pinfunction "1_1") (pintype "passive"))
      (node (ref "IC1") (pin "3") (pinfunction "CT_14_3") (pintype "input"))
      (node (ref "R22") (pin "2") (pinfunction "2_2") (pintype "passive"))
    )
    (net (code "55") (name "CT_REF") (class "Default")
      (node (ref "C46") (pin "2") (pinfunction "2_2") (pintype "passive"))
      (node (ref "C47") (pin "1") (pinfunction "1_1") (pintype "passive"))
      (node (ref "IC1") (pin "38") (pinfunction "CT_REF_38") (pintype "input"))
      (node (ref "R63") (pin "2") (pinfunction "2_2") (pintype "passive"))
    )
    (net (code "56") (name "DSG_FET") (class "Default")
      (node (ref "IC9") (pin "5") (pinfunction "VO_5") (pintype "power_in"))
      (node (ref "R92") (pin "2") (pinfunction "2_2") (pintype "passive"))
      (node (ref "T1") (pin "1") (pinfunction "G_1") (pintype "passive"))
      (node (ref "T2") (pin "1") (pinfunction "G_1") (pintype "passive"))
    )
    (net (code "57") (name "DSG_GATE") (class "Default")
      (node (ref "JP4") (pin "8") (pinfunction "8_8") (pintype "passive"))
      (node (ref "R105") (pin "1") (pinfunction "1_1") (pintype "passive"))
    )
    (net (code "58") (name "FB") (class "Default")
      (node (ref "C66") (pin "2") (pinfunction "2_2") (pintype "passive"))
      (node (ref "C88") (pin "2") (pinfunction "2_2") (pintype "passive"))
      (node (ref "C89") (pin "1") (pinfunction "1_1") (pintype "passive"))
      (node (ref "IC3") (pin "27") (pinfunction "FB_27") (pintype "input"))
      (node (ref "R85") (pin "2") (pinfunction "2_2") (pintype "passive"))
      (node (ref "R86") (pin "1") (pinfunction "1_1") (pintype "passive"))
    )
    (net (code "59") (name "FLOUT") (class "Default")
      (node (ref "IC2") (pin "4") (pinfunction "C_4") (pintype "bidirectional"))
      (node (ref "JP6") (pin "7") (pinfunction "7_7") (pintype "passive"))
      (node (ref "R109") (pin "1") (pinfunction "1_1") (pintype "passive"))
    )
    (net (code "60") (name "GATE") (class "Default")
      (node (ref "D10") (pin "K") (pinfunction "K_K") (pintype "passive"))
      (node (ref "D11") (pin "K") (pinfunction "K_K") (pintype "passive"))
      (node (ref "R93") (pin "1") (pinfunction "1_1") (pintype "passive"))
      (node (ref "R94") (pin "2") (pinfunction "2_2") (pintype "passive"))
      (node (ref "T3") (pin "1") (pinfunction "G_1") (pintype "passive"))
      (node (ref "T4") (pin "1") (pinfunction "G_1") (pintype "passive"))
    )
    (net (code "61") (name "GND") (class "Default")
      (node (ref "C1") (pin "2") (pinfunction "2_2") (pintype "passive"))
      (node (ref "C10") (pin "2") (pinfunction "2_2") (pintype "passive"))
      (node (ref "C11") (pin "2") (pinfunction "2_2") (pintype "passive"))
      (node (ref "C12") (pin "2") (pinfunction "2_2") (pintype "passive"))
      (node (ref "C13") (pin "2") (pinfunction "2_2") (pintype "passive"))
      (node (ref "C14") (pin "2") (pinfunction "2_2") (pintype "passive"))
      (node (ref "C2") (pin "2") (pinfunction "2_2") (pintype "passive"))
      (node (ref "C22") (pin "2") (pinfunction "2_2") (pintype "passive"))
      (node (ref "C23") (pin "2") (pinfunction "2_2") (pintype "passive"))
      (node (ref "C24") (pin "2") (pinfunction "2_2") (pintype "passive"))
      (node (ref "C25") (pin "2") (pinfunction "2_2") (pintype "passive"))
      (node (ref "C26") (pin "2") (pinfunction "2_2") (pintype "passive"))
      (node (ref "C27") (pin "2") (pinfunction "2_2") (pintype "passive"))
      (node (ref "C28") (pin "2") (pinfunction "2_2") (pintype "passive"))
      (node (ref "C29") (pin "2") (pinfunction "2_2") (pintype "passive"))
      (node (ref "C3") (pin "2") (pinfunction "2_2") (pintype "passive"))
      (node (ref "C30") (pin "2") (pinfunction "2_2") (pintype "passive"))
      (node (ref "C31") (pin "2") (pinfunction "2_2") (pintype "passive"))
      (node (ref "C32") (pin "2") (pinfunction "2_2") (pintype "passive"))
      (node (ref "C33") (pin "2") (pinfunction "2_2") (pintype "passive"))
      (node (ref "C34") (pin "2") (pinfunction "2_2") (pintype "passive"))
      (node (ref "C35") (pin "2") (pinfunction "2_2") (pintype "passive"))
      (node (ref "C36") (pin "2") (pinfunction "2_2") (pintype "passive"))
      (node (ref "C37") (pin "2") (pinfunction "2_2") (pintype "passive"))
      (node (ref "C38") (pin "2") (pinfunction "2_2") (pintype "passive"))
      (node (ref "C39") (pin "2") (pinfunction "2_2") (pintype "passive"))
      (node (ref "C4") (pin "2") (pinfunction "2_2") (pintype "passive"))
      (node (ref "C47") (pin "2") (pinfunction "2_2") (pintype "passive"))
      (node (ref "C48") (pin "2") (pinfunction "2_2") (pintype "passive"))
      (node (ref "C49") (pin "2") (pinfunction "2_2") (pintype "passive"))
      (node (ref "C5") (pin "2") (pinfunction "2_2") (pintype "passive"))
      (node (ref "C50") (pin "2") (pinfunction "2_2") (pintype "passive"))
      (node (ref "C51") (pin "2") (pinfunction "2_2") (pintype "passive"))
      (node (ref "C52") (pin "2") (pinfunction "2_2") (pintype "passive"))
      (node (ref "C53") (pin "2") (pinfunction "2_2") (pintype "passive"))
      (node (ref "C54") (pin "2") (pinfunction "2_2") (pintype "passive"))
      (node (ref "C55") (pin "2") (pinfunction "2_2") (pintype "passive"))
      (node (ref "C56") (pin "2") (pinfunction "2_2") (pintype "passive"))
      (node (ref "C57") (pin "2") (pinfunction "2_2") (pintype "passive"))
      (node (ref "C58") (pin "2") (pinfunction "2_2") (pintype "passive"))
      (node (ref "C59") (pin "2") (pinfunction "2_2") (pintype "passive"))
      (node (ref "C6") (pin "2") (pinfunction "2_2") (pintype "passive"))
      (node (ref "C60") (pin "2") (pinfunction "2_2") (pintype "passive"))
      (node (ref "C61") (pin "2") (pinfunction "2_2") (pintype "passive"))
      (node (ref "C62") (pin "2") (pinfunction "2_2") (pintype "passive"))
      (node (ref "C63") (pin "1") (pinfunction "1_1") (pintype "passive"))
      (node (ref "C64") (pin "1") (pinfunction "1_1") (pintype "passive"))
      (node (ref "C67") (pin "2") (pinfunction "2_2") (pintype "passive"))
      (node (ref "C68") (pin "2") (pinfunction "2_2") (pintype "passive"))
      (node (ref "C69") (pin "1") (pinfunction "1_1") (pintype "passive"))
      (node (ref "C7") (pin "2") (pinfunction "2_2") (pintype "passive"))
      (node (ref "C70") (pin "1") (pinfunction "1_1") (pintype "passive"))
      (node (ref "C71") (pin "2") (pinfunction "2_2") (pintype "passive"))
      (node (ref "C72") (pin "2") (pinfunction "2_2") (pintype "passive"))
      (node (ref "C73") (pin "2") (pinfunction "2_2") (pintype "passive"))
      (node (ref "C74") (pin "2") (pinfunction "2_2") (pintype "passive"))
      (node (ref "C76") (pin "2") (pinfunction "2_2") (pintype "passive"))
      (node (ref "C77") (pin "2") (pinfunction "2_2") (pintype "passive"))
      (node (ref "C78") (pin "1") (pinfunction "1_1") (pintype "passive"))
      (node (ref "C79") (pin "2") (pinfunction "2_2") (pintype "passive"))
      (node (ref "C8") (pin "2") (pinfunction "2_2") (pintype "passive"))
      (node (ref "C81") (pin "1") (pinfunction "1_1") (pintype "passive"))
      (node (ref "C82") (pin "1") (pinfunction "1_1") (pintype "passive"))
      (node (ref "C83") (pin "2") (pinfunction "2_2") (pintype "passive"))
      (node (ref "C84") (pin "2") (pinfunction "2_2") (pintype "passive"))
      (node (ref "C85") (pin "2") (pinfunction "2_2") (pintype "passive"))
      (node (ref "C87") (pin "1") (pinfunction "1_1") (pintype "passive"))
      (node (ref "C89") (pin "2") (pinfunction "2_2") (pintype "passive"))
      (node (ref "C9") (pin "2") (pinfunction "2_2") (pintype "passive"))
      (node (ref "C90") (pin "-") (pinfunction "-_-") (pintype "passive"))
      (node (ref "C91") (pin "-") (pinfunction "-_-") (pintype "passive"))
      (node (ref "CG") (pin "P$1") (pinfunction "P$1_P$1") (pintype "passive"))
      (node (ref "D14") (pin "A") (pinfunction "A_A") (pintype "passive"))
      (node (ref "D15") (pin "A") (pinfunction "A_A") (pintype "passive"))
      (node (ref "D16") (pin "A") (pinfunction "A_A") (pintype "passive"))
      (node (ref "D5") (pin "A") (pinfunction "A_A") (pintype "passive"))
      (node (ref "D7") (pin "K") (pinfunction "K_K") (pintype "passive"))
      (node (ref "D9") (pin "K") (pinfunction "K_K") (pintype "passive"))
      (node (ref "GND") (pin "P$1") (pinfunction "P$1_P$1") (pintype "passive"))
      (node (ref "GND@1") (pin "P$1") (pinfunction "P$1_P$1") (pintype "passive"))
      (node (ref "IC1") (pin "44") (pinfunction "CGND_44") (pintype "power_in"))
      (node (ref "IC1") (pin "58") (pinfunction "AGND_58") (pintype "power_in"))
      (node (ref "IC1") (pin "59") (pinfunction "DGND_59") (pintype "power_in"))
      (node (ref "IC1") (pin "64") (pinfunction "GNDREF_64") (pintype "power_in"))
      (node (ref "IC1") (pin "65") (pinfunction "GNDFLAG_65") (pintype "power_in"))
      (node (ref "IC10") (pin "3") (pinfunction "CATHODE_3") (pintype "power_in"))
      (node (ref "IC10") (pin "4") (pinfunction "GND_4") (pintype "power_in"))
      (node (ref "IC11") (pin "3") (pinfunction "CATHODE_3") (pintype "power_in"))
      (node (ref "IC11") (pin "4") (pinfunction "GND_4") (pintype "power_in"))
      (node (ref "IC2") (pin "2") (pinfunction "K_2") (pintype "bidirectional"))
      (node (ref "IC2") (pin "3") (pinfunction "E_3") (pintype "bidirectional"))
      (node (ref "IC3") (pin "16") (pinfunction "PGND_16") (pintype "power_in"))
      (node (ref "IC3") (pin "17") (pinfunction "PGND_17") (pintype "power_in"))
      (node (ref "IC3") (pin "18") (pinfunction "PGND_18") (pintype "power_in"))
      (node (ref "IC3") (pin "19") (pinfunction "PGND_19") (pintype "power_in"))
      (node (ref "IC3") (pin "2") (pinfunction "PGND_2") (pintype "power_in"))
      (node (ref "IC3") (pin "22") (pinfunction "PGND_22") (pintype "power_in"))
      (node (ref "IC3") (pin "28") (pinfunction "AGND_28") (pintype "power_in"))
      (node (ref "IC3") (pin "29") (pinfunction "PGND_29") (pintype "power_in"))
      (node (ref "IC3") (pin "33") (pinfunction "PGND_33") (pintype "power_in"))
      (node (ref "IC7") (pin "3") (pinfunction "E_3") (pintype "bidirectional"))
      (node (ref "IC8") (pin "2") (pinfunction "K_2") (pintype "bidirectional"))
      (node (ref "IC9") (pin "3") (pinfunction "CATHODE_3") (pintype "power_in"))
      (node (ref "IC9") (pin "4") (pinfunction "GND_4") (pintype "power_in"))
      (node (ref "JP3") (pin "4") (pinfunction "4_4") (pintype "passive"))
      (node (ref "JP4") (pin "14") (pinfunction "14_14") (pintype "passive"))
      (node (ref "JP4") (pin "15") (pinfunction "15_15") (pintype "passive"))
      (node (ref "JP6") (pin "12") (pinfunction "12_12") (pintype "passive"))
      (node (ref "JP6") (pin "8") (pinfunction "8_8") (pintype "passive"))
      (node (ref "JP6") (pin "9") (pinfunction "9_9") (pintype "passive"))
      (node (ref "Q1") (pin "1") (pinfunction "G_1") (pintype "input"))
      (node (ref "Q3") (pin "2") (pinfunction "E_2") (pintype "passive"))
      (node (ref "Q4") (pin "2") (pinfunction "E_2") (pintype "passive"))
      (node (ref "Q5") (pin "2") (pinfunction "E_2") (pintype "passive"))
      (node (ref "Q6") (pin "2") (pinfunction "E_2") (pintype "passive"))
      (node (ref "Q7") (pin "2") (pinfunction "E_2") (pintype "passive"))
      (node (ref "Q8") (pin "2") (pinfunction "E_2") (pintype "passive"))
      (node (ref "R100") (pin "2") (pinfunction "2_2") (pintype "passive"))
      (node (ref "R118") (pin "2") (pinfunction "2_2") (pintype "passive"))
      (node (ref "R120") (pin "2") (pinfunction "2_2") (pintype "passive"))
      (node (ref "R122") (pin "2") (pinfunction "2_2") (pintype "passive"))
      (node (ref "R123") (pin "2") (pinfunction "2_2") (pintype "passive"))
      (node (ref "R124") (pin "2") (pinfunction "2_2") (pintype "passive"))
      (node (ref "R30") (pin "2") (pinfunction "2_2") (pintype "passive"))
      (node (ref "R34") (pin "2") (pinfunction "2_2") (pintype "passive"))
      (node (ref "R86") (pin "2") (pinfunction "2_2") (pintype "passive"))
      (node (ref "R89") (pin "2") (pinfunction "2_2") (pintype "passive"))
      (node (ref "TP8") (pin "P$1") (pinfunction "P$1_P$1") (pintype "passive"))
      (node (ref "U1") (pin "1") (pinfunction "ADJ/GND_1") (pintype "bidirectional"))
      (node (ref "U1") (pin "4") (pinfunction "ADJ/GND_4") (pintype "bidirectional"))
      (node (ref "U2") (pin "1") (pinfunction "ADJ/GND_1") (pintype "bidirectional"))
      (node (ref "U2") (pin "4") (pinfunction "ADJ/GND_4") (pintype "bidirectional"))
    )
    (net (code "62") (name "GPIO0") (class "Default")
      (node (ref "C59") (pin "1") (pinfunction "1_1") (pintype "passive"))
      (node (ref "IC1") (pin "49") (pinfunction "GPIO0_49") (pintype "bidirectional"))
      (node (ref "R72") (pin "1") (pinfunction "1_1") (pintype "passive"))
    )
    (net (code "63") (name "GPIO1") (class "Default")
      (node (ref "C55") (pin "1") (pinfunction "1_1") (pintype "passive"))
      (node (ref "IC1") (pin "50") (pinfunction "GPIO1_50") (pintype "bidirectional"))
      (node (ref "R73") (pin "1") (pinfunction "1_1") (pintype "passive"))
    )
    (net (code "64") (name "GPIO2") (class "Default")
      (node (ref "C56") (pin "1") (pinfunction "1_1") (pintype "passive"))
      (node (ref "IC1") (pin "51") (pinfunction "GPIO2_51") (pintype "bidirectional"))
      (node (ref "R74") (pin "1") (pinfunction "1_1") (pintype "passive"))
    )
    (net (code "65") (name "GPIO3") (class "Default")
      (node (ref "C57") (pin "1") (pinfunction "1_1") (pintype "passive"))
      (node (ref "IC1") (pin "52") (pinfunction "GPIO3_52") (pintype "bidirectional"))
      (node (ref "R75") (pin "1") (pinfunction "1_1") (pintype "passive"))
    )
    (net (code "66") (name "GPIO4") (class "Default")
      (node (ref "C58") (pin "1") (pinfunction "1_1") (pintype "passive"))
      (node (ref "IC1") (pin "53") (pinfunction "GPIO4_53") (pintype "bidirectional"))
      (node (ref "R76") (pin "1") (pinfunction "1_1") (pintype "passive"))
    )
    (net (code "67") (name "GPIO5") (class "Default")
      (node (ref "C62") (pin "1") (pinfunction "1_1") (pintype "passive"))
      (node (ref "IC1") (pin "54") (pinfunction "GPIO5_54") (pintype "bidirectional"))
      (node (ref "R77") (pin "1") (pinfunction "1_1") (pintype "passive"))
    )
    (net (code "68") (name "GPIO6") (class "Default")
      (node (ref "C60") (pin "1") (pinfunction "1_1") (pintype "passive"))
      (node (ref "IC1") (pin "55") (pinfunction "GPIO6_55") (pintype "bidirectional"))
      (node (ref "R78") (pin "1") (pinfunction "1_1") (pintype "passive"))
    )
    (net (code "69") (name "ILIM") (class "Default")
      (node (ref "IC3") (pin "1") (pinfunction "ILIM_1") (pintype "input"))
      (node (ref "R82") (pin "1") (pinfunction "1_1") (pintype "passive"))
    )
    (net (code "70") (name "INTL_IN2") (class "Default")
      (node (ref "D12") (pin "A") (pinfunction "A_A") (pintype "passive"))
      (node (ref "KI") (pin "P$1") (pinfunction "P$1_P$1") (pintype "passive"))
    )
    (net (code "71") (name "ISENSE+") (class "Default")
      (node (ref "C71") (pin "1") (pinfunction "1_1") (pintype "passive"))
      (node (ref "C75") (pin "1") (pinfunction "1_1") (pintype "passive"))
      (node (ref "IC1") (pin "56") (pinfunction "ISENSE+_56") (pintype "input"))
      (node (ref "R87") (pin "2") (pinfunction "2_2") (pintype "passive"))
    )
    (net (code "72") (name "ISENSE-") (class "Default")
      (node (ref "C72") (pin "1") (pinfunction "1_1") (pintype "passive"))
      (node (ref "C75") (pin "2") (pinfunction "2_2") (pintype "passive"))
      (node (ref "IC1") (pin "57") (pinfunction "ISENSE-_57") (pintype "input"))
      (node (ref "R88") (pin "2") (pinfunction "2_2") (pintype "passive"))
    )
    (net (code "73") (name "KEY-IN") (class "Default")
      (node (ref "D12") (pin "K") (pinfunction "K_K") (pintype "passive"))
      (node (ref "D13") (pin "K") (pinfunction "K_K") (pintype "passive"))
      (node (ref "R99") (pin "1") (pinfunction "1_1") (pintype "passive"))
    )
    (net (code "74") (name "MISO") (class "Default")
      (node (ref "IC1") (pin "42") (pinfunction "SO_42") (pintype "output"))
      (node (ref "R121") (pin "2") (pinfunction "2_2") (pintype "passive"))
    )
    (net (code "75") (name "MOSI") (class "Default")
      (node (ref "IC1") (pin "47") (pinfunction "SI/RDTX_IN+_47") (pintype "bidirectional"))
      (node (ref "JP6") (pin "1") (pinfunction "1_1") (pintype "passive"))
    )
    (net (code "76") (name "Net-(C8-Pad1)") (class "Default")
      (node (ref "C8") (pin "1") (pinfunction "1_1") (pintype "passive"))
      (node (ref "R15") (pin "2") (pinfunction "2_2") (pintype "passive"))
      (node (ref "R23") (pin "1") (pinfunction "1_1") (pintype "passive"))
    )
    (net (code "77") (name "Net-(C9-Pad1)") (class "Default")
      (node (ref "C9") (pin "1") (pinfunction "1_1") (pintype "passive"))
      (node (ref "R16") (pin "2") (pinfunction "2_2") (pintype "passive"))
      (node (ref "R25") (pin "1") (pinfunction "1_1") (pintype "passive"))
    )
    (net (code "78") (name "Net-(C10-Pad1)") (class "Default")
      (node (ref "C10") (pin "1") (pinfunction "1_1") (pintype "passive"))
      (node (ref "R17") (pin "2") (pinfunction "2_2") (pintype "passive"))
      (node (ref "R27") (pin "1") (pinfunction "1_1") (pintype "passive"))
    )
    (net (code "79") (name "Net-(C11-Pad1)") (class "Default")
      (node (ref "C11") (pin "1") (pinfunction "1_1") (pintype "passive"))
      (node (ref "R18") (pin "2") (pinfunction "2_2") (pintype "passive"))
      (node (ref "R28") (pin "1") (pinfunction "1_1") (pintype "passive"))
    )
    (net (code "80") (name "Net-(C12-Pad1)") (class "Default")
      (node (ref "C12") (pin "1") (pinfunction "1_1") (pintype "passive"))
      (node (ref "R19") (pin "2") (pinfunction "2_2") (pintype "passive"))
      (node (ref "R22") (pin "1") (pinfunction "1_1") (pintype "passive"))
    )
    (net (code "81") (name "Net-(C13-Pad1)") (class "Default")
      (node (ref "C13") (pin "1") (pinfunction "1_1") (pintype "passive"))
      (node (ref "R20") (pin "2") (pinfunction "2_2") (pintype "passive"))
      (node (ref "R24") (pin "1") (pinfunction "1_1") (pintype "passive"))
    )
    (net (code "82") (name "Net-(C14-Pad1)") (class "Default")
      (node (ref "C14") (pin "1") (pinfunction "1_1") (pintype "passive"))
      (node (ref "R21") (pin "2") (pinfunction "2_2") (pintype "passive"))
      (node (ref "R26") (pin "1") (pinfunction "1_1") (pintype "passive"))
    )
    (net (code "83") (name "Net-(C32-Pad1)") (class "Default")
      (node (ref "C32") (pin "1") (pinfunction "1_1") (pintype "passive"))
      (node (ref "R44") (pin "2") (pinfunction "2_2") (pintype "passive"))
      (node (ref "R58") (pin "1") (pinfunction "1_1") (pintype "passive"))
    )
    (net (code "84") (name "Net-(C33-Pad1)") (class "Default")
      (node (ref "C33") (pin "1") (pinfunction "1_1") (pintype "passive"))
      (node (ref "R45") (pin "2") (pinfunction "2_2") (pintype "passive"))
      (node (ref "R63") (pin "1") (pinfunction "1_1") (pintype "passive"))
    )
    (net (code "85") (name "Net-(C34-Pad1)") (class "Default")
      (node (ref "C34") (pin "1") (pinfunction "1_1") (pintype "passive"))
      (node (ref "R50") (pin "2") (pinfunction "2_2") (pintype "passive"))
      (node (ref "R56") (pin "1") (pinfunction "1_1") (pintype "passive"))
    )
    (net (code "86") (name "Net-(C35-Pad1)") (class "Default")
      (node (ref "C35") (pin "1") (pinfunction "1_1") (pintype "passive"))
      (node (ref "R51") (pin "2") (pinfunction "2_2") (pintype "passive"))
      (node (ref "R57") (pin "1") (pinfunction "1_1") (pintype "passive"))
    )
    (net (code "87") (name "Net-(C36-Pad1)") (class "Default")
      (node (ref "C36") (pin "1") (pinfunction "1_1") (pintype "passive"))
      (node (ref "R52") (pin "2") (pinfunction "2_2") (pintype "passive"))
      (node (ref "R59") (pin "1") (pinfunction "1_1") (pintype "passive"))
    )
    (net (code "88") (name "Net-(C37-Pad1)") (class "Default")
      (node (ref "C37") (pin "1") (pinfunction "1_1") (pintype "passive"))
      (node (ref "R53") (pin "2") (pinfunction "2_2") (pintype "passive"))
      (node (ref "R60") (pin "1") (pinfunction "1_1") (pintype "passive"))
    )
    (net (code "89") (name "Net-(C38-Pad1)") (class "Default")
      (node (ref "C38") (pin "1") (pinfunction "1_1") (pintype "passive"))
      (node (ref "R54") (pin "2") (pinfunction "2_2") (pintype "passive"))
      (node (ref "R62") (pin "1") (pinfunction "1_1") (pintype "passive"))
    )
    (net (code "90") (name "Net-(C39-Pad1)") (class "Default")
      (node (ref "C39") (pin "1") (pinfunction "1_1") (pintype "passive"))
      (node (ref "R55") (pin "2") (pinfunction "2_2") (pintype "passive"))
      (node (ref "R61") (pin "1") (pinfunction "1_1") (pintype "passive"))
    )
    (net (code "91") (name "Net-(C48-Pad1)") (class "Default")
      (node (ref "C48") (pin "1") (pinfunction "1_1") (pintype "passive"))
      (node (ref "R64") (pin "1") (pinfunction "1_1") (pintype "passive"))
      (node (ref "R72") (pin "2") (pinfunction "2_2") (pintype "passive"))
      (node (ref "TP2") (pin "P$1") (pinfunction "P$1_P$1") (pintype "passive"))
    )
    (net (code "92") (name "Net-(C49-Pad1)") (class "Default")
      (node (ref "C49") (pin "1") (pinfunction "1_1") (pintype "passive"))
      (node (ref "R65") (pin "1") (pinfunction "1_1") (pintype "passive"))
      (node (ref "R73") (pin "2") (pinfunction "2_2") (pintype "passive"))
      (node (ref "TP3") (pin "P$1") (pinfunction "P$1_P$1") (pintype "passive"))
    )
    (net (code "93") (name "Net-(C50-Pad1)") (class "Default")
      (node (ref "C50") (pin "1") (pinfunction "1_1") (pintype "passive"))
      (node (ref "R67") (pin "1") (pinfunction "1_1") (pintype "passive"))
      (node (ref "R74") (pin "2") (pinfunction "2_2") (pintype "passive"))
      (node (ref "TP4") (pin "P$1") (pinfunction "P$1_P$1") (pintype "passive"))
    )
    (net (code "94") (name "Net-(C51-Pad1)") (class "Default")
      (node (ref "C51") (pin "1") (pinfunction "1_1") (pintype "passive"))
      (node (ref "R70") (pin "1") (pinfunction "1_1") (pintype "passive"))
      (node (ref "R77") (pin "2") (pinfunction "2_2") (pintype "passive"))
      (node (ref "TP7") (pin "P$1") (pinfunction "P$1_P$1") (pintype "passive"))
    )
    (net (code "95") (name "Net-(C52-Pad1)") (class "Default")
      (node (ref "C52") (pin "1") (pinfunction "1_1") (pintype "passive"))
      (node (ref "R68") (pin "1") (pinfunction "1_1") (pintype "passive"))
      (node (ref "R75") (pin "2") (pinfunction "2_2") (pintype "passive"))
      (node (ref "TP5") (pin "P$1") (pinfunction "P$1_P$1") (pintype "passive"))
    )
    (net (code "96") (name "Net-(C53-Pad1)") (class "Default")
      (node (ref "C53") (pin "1") (pinfunction "1_1") (pintype "passive"))
      (node (ref "R69") (pin "1") (pinfunction "1_1") (pintype "passive"))
      (node (ref "R76") (pin "2") (pinfunction "2_2") (pintype "passive"))
      (node (ref "TP6") (pin "P$1") (pinfunction "P$1_P$1") (pintype "passive"))
    )
    (net (code "97") (name "Net-(C54-Pad1)") (class "Default")
      (node (ref "C54") (pin "1") (pinfunction "1_1") (pintype "passive"))
      (node (ref "R71") (pin "1") (pinfunction "1_1") (pintype "passive"))
      (node (ref "R78") (pin "2") (pinfunction "2_2") (pintype "passive"))
      (node (ref "TP9") (pin "P$1") (pinfunction "P$1_P$1") (pintype "passive"))
    )
    (net (code "98") (name "Net-(C65-Pad2)") (class "Default")
      (node (ref "C65") (pin "2") (pinfunction "2_2") (pintype "passive"))
      (node (ref "R108") (pin "1") (pinfunction "1_1") (pintype "passive"))
    )
    (net (code "99") (name "Net-(C66-Pad1)") (class "Default")
      (node (ref "C66") (pin "1") (pinfunction "1_1") (pintype "passive"))
      (node (ref "R83") (pin "2") (pinfunction "2_2") (pintype "passive"))
    )
    (net (code "100") (name "Net-(C67-Pad1)") (class "Default")
      (node (ref "C67") (pin "1") (pinfunction "1_1") (pintype "passive"))
      (node (ref "D6") (pin "K") (pinfunction "K_K") (pintype "passive"))
      (node (ref "R81") (pin "5") (pinfunction "5_5") (pintype "bidirectional"))
      (node (ref "R84") (pin "5") (pinfunction "5_5") (pintype "bidirectional"))
      (node (ref "R87") (pin "1") (pinfunction "1_1") (pintype "passive"))
    )
    (net (code "101") (name "Net-(C68-Pad1)") (class "Default")
      (node (ref "C68") (pin "1") (pinfunction "1_1") (pintype "passive"))
      (node (ref "D8") (pin "K") (pinfunction "K_K") (pintype "passive"))
      (node (ref "R81") (pin "2") (pinfunction "2_2") (pintype "bidirectional"))
      (node (ref "R84") (pin "2") (pinfunction "2_2") (pintype "bidirectional"))
      (node (ref "R88") (pin "1") (pinfunction "1_1") (pintype "passive"))
    )
    (net (code "102") (name "Net-(CELL1+-S)") (class "Default")
      (node (ref "CELL1+") (pin "P$1") (pinfunction "S_P$1") (pintype "power_in"))
      (node (ref "R41") (pin "1") (pinfunction "1_1") (pintype "passive"))
    )
    (net (code "103") (name "Net-(CELL2+-S)") (class "Default")
      (node (ref "CELL2+") (pin "P$1") (pinfunction "S_P$1") (pintype "power_in"))
      (node (ref "R37") (pin "1") (pinfunction "1_1") (pintype "passive"))
    )
    (net (code "104") (name "Net-(CELL3+-S)") (class "Default")
      (node (ref "CELL3+") (pin "P$1") (pinfunction "S_P$1") (pintype "power_in"))
      (node (ref "R43") (pin "1") (pinfunction "1_1") (pintype "passive"))
    )
    (net (code "105") (name "Net-(CELL4+-S)") (class "Default")
      (node (ref "CELL4+") (pin "P$1") (pinfunction "S_P$1") (pintype "power_in"))
      (node (ref "R32") (pin "1") (pinfunction "1_1") (pintype "passive"))
    )
    (net (code "106") (name "Net-(CELL5+-S)") (class "Default")
      (node (ref "CELL5+") (pin "P$1") (pinfunction "S_P$1") (pintype "power_in"))
      (node (ref "R33") (pin "1") (pinfunction "1_1") (pintype "passive"))
    )
    (net (code "107") (name "Net-(CELL6+-S)") (class "Default")
      (node (ref "CELL6+") (pin "P$1") (pinfunction "S_P$1") (pintype "power_in"))
      (node (ref "R36") (pin "1") (pinfunction "1_1") (pintype "passive"))
    )
    (net (code "108") (name "Net-(CELL7+-S)") (class "Default")
      (node (ref "CELL7+") (pin "P$1") (pinfunction "S_P$1") (pintype "power_in"))
      (node (ref "R42") (pin "1") (pinfunction "1_1") (pintype "passive"))
    )
    (net (code "109") (name "Net-(CELL8+-S)") (class "Default")
      (node (ref "CELL8+") (pin "P$1") (pinfunction "S_P$1") (pintype "power_in"))
      (node (ref "R2") (pin "1") (pinfunction "1_1") (pintype "passive"))
    )
    (net (code "110") (name "Net-(CELL9+-S)") (class "Default")
      (node (ref "CELL9+") (pin "P$1") (pinfunction "S_P$1") (pintype "power_in"))
      (node (ref "R10") (pin "2") (pinfunction "2_2") (pintype "passive"))
    )
    (net (code "111") (name "Net-(CELL10+-S)") (class "Default")
      (node (ref "CELL10+") (pin "P$1") (pinfunction "S_P$1") (pintype "power_in"))
      (node (ref "R4") (pin "1") (pinfunction "1_1") (pintype "passive"))
    )
    (net (code "112") (name "Net-(CELL11+-S)") (class "Default")
      (node (ref "CELL11+") (pin "P$1") (pinfunction "S_P$1") (pintype "power_in"))
      (node (ref "R9") (pin "1") (pinfunction "1_1") (pintype "passive"))
    )
    (net (code "113") (name "Net-(CELL12+-S)") (class "Default")
      (node (ref "CELL12+") (pin "P$1") (pinfunction "S_P$1") (pintype "power_in"))
      (node (ref "R1") (pin "1") (pinfunction "1_1") (pintype "passive"))
    )
    (net (code "114") (name "Net-(CELL13+-S)") (class "Default")
      (node (ref "CELL13+") (pin "P$1") (pinfunction "S_P$1") (pintype "power_in"))
      (node (ref "R8") (pin "1") (pinfunction "1_1") (pintype "passive"))
    )
    (net (code "115") (name "Net-(D6-PadA)") (class "Default")
      (node (ref "D6") (pin "A") (pinfunction "A_A") (pintype "passive"))
      (node (ref "D7") (pin "A") (pinfunction "A_A") (pintype "passive"))
    )
    (net (code "116") (name "Net-(D8-PadA)") (class "Default")
      (node (ref "D8") (pin "A") (pinfunction "A_A") (pintype "passive"))
      (node (ref "D9") (pin "A") (pinfunction "A_A") (pintype "passive"))
    )
    (net (code "117") (name "Net-(D13-PadA)") (class "Default")
      (node (ref "D13") (pin "A") (pinfunction "A_A") (pintype "passive"))
      (node (ref "JP1") (pin "1") (pinfunction "1_1") (pintype "passive"))
    )
    (net (code "118") (name "Net-(D20-PadA)") (class "Default")
      (node (ref "D20") (pin "A") (pinfunction "A_A") (pintype "passive"))
      (node (ref "D3") (pin "K") (pinfunction "K_K") (pintype "passive"))
    )
    (net (code "119") (name "Net-(D21-PadA)") (class "Default")
      (node (ref "D21") (pin "A") (pinfunction "A_A") (pintype "passive"))
      (node (ref "R119") (pin "2") (pinfunction "2_2") (pintype "passive"))
      (node (ref "R95") (pin "1") (pinfunction "1_1") (pintype "passive"))
    )
    (net (code "120") (name "Net-(IC1-FAULT)") (class "Default")
      (node (ref "IC1") (pin "40") (pinfunction "FAULT_40") (pintype "output"))
      (node (ref "R31") (pin "1") (pinfunction "1_1") (pintype "passive"))
    )
    (net (code "121") (name "Net-(IC1-SPI_COM_EN)") (class "Default")
      (node (ref "IC1") (pin "39") (pinfunction "SPI_COM_EN_39") (pintype "input"))
      (node (ref "R29") (pin "1") (pinfunction "1_1") (pintype "passive"))
    )
    (net (code "122") (name "Net-(IC1-VANA)") (class "Default")
      (node (ref "C23") (pin "1") (pinfunction "1_1") (pintype "passive"))
      (node (ref "IC1") (pin "60") (pinfunction "VANA_60") (pintype "output"))
    )
    (net (code "123") (name "Net-(IC2B-A)") (class "Default")
      (node (ref "IC2") (pin "1") (pinfunction "A_1") (pintype "bidirectional"))
      (node (ref "R31") (pin "2") (pinfunction "2_2") (pintype "passive"))
    )
    (net (code "124") (name "Net-(IC3-EN)") (class "Default")
      (node (ref "IC3") (pin "24") (pinfunction "EN_24") (pintype "input"))
      (node (ref "R107") (pin "1") (pinfunction "1_1") (pintype "passive"))
    )
    (net (code "125") (name "Net-(IC3-EXTVDD)") (class "Default")
      (node (ref "C73") (pin "1") (pinfunction "1_1") (pintype "passive"))
      (node (ref "IC3") (pin "23") (pinfunction "EXTVDD_23") (pintype "power_in"))
    )
    (net (code "126") (name "Net-(IC3-FREQ)") (class "Default")
      (node (ref "IC3") (pin "25") (pinfunction "FREQ_25") (pintype "input"))
      (node (ref "R89") (pin "1") (pinfunction "1_1") (pintype "passive"))
      (node (ref "R90") (pin "1") (pinfunction "1_1") (pintype "passive"))
    )
    (net (code "127") (name "Net-(IC3-MODE)") (class "Default")
      (node (ref "IC3") (pin "26") (pinfunction "MODE_26") (pintype "input"))
      (node (ref "R118") (pin "1") (pinfunction "1_1") (pintype "passive"))
    )
    (net (code "128") (name "Net-(IC3-PVDD)") (class "Default")
      (node (ref "C77") (pin "1") (pinfunction "1_1") (pintype "passive"))
      (node (ref "IC3") (pin "21") (pinfunction "PVDD_21") (pintype "power_in"))
      (node (ref "R91") (pin "1") (pinfunction "1_1") (pintype "passive"))
    )
    (net (code "129") (name "Net-(IC3-SVIN)") (class "Default")
      (node (ref "C74") (pin "1") (pinfunction "1_1") (pintype "passive"))
      (node (ref "IC3") (pin "31") (pinfunction "SVIN_31") (pintype "input"))
      (node (ref "R79") (pin "2") (pinfunction "2_2") (pintype "passive"))
    )
    (net (code "130") (name "Net-(IC3-VDD)") (class "Default")
      (node (ref "C76") (pin "1") (pinfunction "1_1") (pintype "passive"))
      (node (ref "IC3") (pin "30") (pinfunction "VDD_30") (pintype "power_in"))
      (node (ref "R91") (pin "2") (pinfunction "2_2") (pintype "passive"))
    )
    (net (code "131") (name "Net-(IC7B-K)") (class "Default")
      (node (ref "IC7") (pin "2") (pinfunction "K_2") (pintype "bidirectional"))
      (node (ref "R95") (pin "2") (pinfunction "2_2") (pintype "passive"))
    )
    (net (code "132") (name "Net-(IC8A-C)") (class "Default")
      (node (ref "IC8") (pin "4") (pinfunction "C_4") (pintype "bidirectional"))
      (node (ref "JP7") (pin "1") (pinfunction "1_1") (pintype "passive"))
    )
    (net (code "133") (name "Net-(IC8A-E)") (class "Default")
      (node (ref "IC8") (pin "3") (pinfunction "E_3") (pintype "bidirectional"))
      (node (ref "JP7") (pin "2") (pinfunction "2_2") (pintype "passive"))
    )
    (net (code "134") (name "Net-(IC8B-A)") (class "Default")
      (node (ref "IC8") (pin "1") (pinfunction "A_1") (pintype "bidirectional"))
      (node (ref "R97") (pin "2") (pinfunction "2_2") (pintype "passive"))
    )
    (net (code "135") (name "Net-(IC9-ANODE)") (class "Default")
      (node (ref "IC9") (pin "1") (pinfunction "ANODE_1") (pintype "power_in"))
      (node (ref "R105") (pin "2") (pinfunction "2_2") (pintype "passive"))
    )
    (net (code "136") (name "Net-(IC10-ANODE)") (class "Default")
      (node (ref "IC10") (pin "1") (pinfunction "ANODE_1") (pintype "power_in"))
      (node (ref "R96") (pin "2") (pinfunction "2_2") (pintype "passive"))
    )
    (net (code "137") (name "Net-(IC11-ANODE)") (class "Default")
      (node (ref "IC11") (pin "1") (pinfunction "ANODE_1") (pintype "power_in"))
      (node (ref "R106") (pin "2") (pinfunction "2_2") (pintype "passive"))
    )
    (net (code "138") (name "Net-(JP6-Pad3)") (class "Default")
      (node (ref "JP6") (pin "3") (pinfunction "3_3") (pintype "passive"))
      (node (ref "R120") (pin "1") (pinfunction "1_1") (pintype "passive"))
      (node (ref "R121") (pin "1") (pinfunction "1_1") (pintype "passive"))
    )
    (net (code "139") (name "Net-(LED1-CG)") (class "Default")
      (node (ref "LED1") (pin "1") (pinfunction "CG_1") (pintype "passive"))
      (node (ref "R117") (pin "1") (pinfunction "1_1") (pintype "passive"))
    )
    (net (code "140") (name "Net-(LED1-CR)") (class "Default")
      (node (ref "LED1") (pin "3") (pinfunction "CR_3") (pintype "passive"))
      (node (ref "R116") (pin "1") (pinfunction "1_1") (pintype "passive"))
    )
    (net (code "141") (name "Net-(LED2-CG)") (class "Default")
      (node (ref "LED2") (pin "1") (pinfunction "CG_1") (pintype "passive"))
      (node (ref "R101") (pin "1") (pinfunction "1_1") (pintype "passive"))
    )
    (net (code "142") (name "Net-(LED2-CR)") (class "Default")
      (node (ref "LED2") (pin "3") (pinfunction "CR_3") (pintype "passive"))
      (node (ref "R102") (pin "1") (pinfunction "1_1") (pintype "passive"))
    )
    (net (code "143") (name "Net-(LED3-C)") (class "Default")
      (node (ref "LED3") (pin "K") (pinfunction "C_K") (pintype "passive"))
      (node (ref "R103") (pin "1") (pinfunction "1_1") (pintype "passive"))
    )
    (net (code "144") (name "Net-(LED4-C)") (class "Default")
      (node (ref "LED4") (pin "K") (pinfunction "C_K") (pintype "passive"))
      (node (ref "R104") (pin "1") (pinfunction "1_1") (pintype "passive"))
    )
    (net (code "145") (name "Net-(Q1-D)") (class "Default")
      (node (ref "D10") (pin "A") (pinfunction "A_A") (pintype "passive"))
      (node (ref "Q1") (pin "3") (pinfunction "D_3") (pintype "power_in"))
      (node (ref "R93") (pin "2") (pinfunction "2_2") (pintype "passive"))
    )
    (net (code "146") (name "Net-(Q2-S)") (class "Default")
      (node (ref "Q2") (pin "2") (pinfunction "S_2") (pintype "passive"))
      (node (ref "R98") (pin "2") (pinfunction "2_2") (pintype "passive"))
    )
    (net (code "147") (name "Net-(Q3-B)") (class "Default")
      (node (ref "Q3") (pin "1") (pinfunction "B_1") (pintype "passive"))
      (node (ref "R80") (pin "1") (pinfunction "1_1") (pintype "passive"))
    )
    (net (code "148") (name "Net-(Q3-C)") (class "Default")
      (node (ref "Q3") (pin "3") (pinfunction "C_3") (pintype "passive"))
      (node (ref "R116") (pin "2") (pinfunction "2_2") (pintype "passive"))
    )
    (net (code "149") (name "Net-(Q4-B)") (class "Default")
      (node (ref "Q4") (pin "1") (pinfunction "B_1") (pintype "passive"))
      (node (ref "R111") (pin "1") (pinfunction "1_1") (pintype "passive"))
    )
    (net (code "150") (name "Net-(Q4-C)") (class "Default")
      (node (ref "Q4") (pin "3") (pinfunction "C_3") (pintype "passive"))
      (node (ref "R117") (pin "2") (pinfunction "2_2") (pintype "passive"))
    )
    (net (code "151") (name "Net-(Q5-B)") (class "Default")
      (node (ref "Q5") (pin "1") (pinfunction "B_1") (pintype "passive"))
      (node (ref "R113") (pin "1") (pinfunction "1_1") (pintype "passive"))
    )
    (net (code "152") (name "Net-(Q5-C)") (class "Default")
      (node (ref "Q5") (pin "3") (pinfunction "C_3") (pintype "passive"))
      (node (ref "R101") (pin "2") (pinfunction "2_2") (pintype "passive"))
    )
    (net (code "153") (name "Net-(Q6-B)") (class "Default")
      (node (ref "Q6") (pin "1") (pinfunction "B_1") (pintype "passive"))
      (node (ref "R112") (pin "1") (pinfunction "1_1") (pintype "passive"))
    )
    (net (code "154") (name "Net-(Q6-C)") (class "Default")
      (node (ref "Q6") (pin "3") (pinfunction "C_3") (pintype "passive"))
      (node (ref "R102") (pin "2") (pinfunction "2_2") (pintype "passive"))
    )
    (net (code "155") (name "Net-(Q7-B)") (class "Default")
      (node (ref "Q7") (pin "1") (pinfunction "B_1") (pintype "passive"))
      (node (ref "R114") (pin "1") (pinfunction "1_1") (pintype "passive"))
    )
    (net (code "156") (name "Net-(Q7-C)") (class "Default")
      (node (ref "Q7") (pin "3") (pinfunction "C_3") (pintype "passive"))
      (node (ref "R103") (pin "2") (pinfunction "2_2") (pintype "passive"))
    )
    (net (code "157") (name "Net-(Q8-B)") (class "Default")
      (node (ref "Q8") (pin "1") (pinfunction "B_1") (pintype "passive"))
      (node (ref "R115") (pin "1") (pinfunction "1_1") (pintype "passive"))
    )
    (net (code "158") (name "Net-(Q8-C)") (class "Default")
      (node (ref "Q8") (pin "3") (pinfunction "C_3") (pintype "passive"))
      (node (ref "R104") (pin "2") (pinfunction "2_2") (pintype "passive"))
    )
    (net (code "159") (name "OLED_SCL") (class "Default")
      (node (ref "JP3") (pin "2") (pinfunction "2_2") (pintype "passive"))
      (node (ref "JP6") (pin "5") (pinfunction "5_5") (pintype "passive"))
    )
    (net (code "160") (name "OLED_SDA") (class "Default")
      (node (ref "JP3") (pin "1") (pinfunction "1_1") (pintype "passive"))
      (node (ref "JP6") (pin "6") (pinfunction "6_6") (pintype "passive"))
    )
    (net (code "161") (name "PCHG_FET") (class "Default")
      (node (ref "IC11") (pin "5") (pinfunction "VO_5") (pintype "power_in"))
      (node (ref "Q2") (pin "1") (pinfunction "G_1") (pintype "passive"))
    )
    (net (code "162") (name "PCHG_GATE") (class "Default")
      (node (ref "JP4") (pin "10") (pinfunction "10_10") (pintype "passive"))
      (node (ref "R106") (pin "1") (pinfunction "1_1") (pintype "passive"))
    )
    (net (code "163") (name "PWR_DRAIN") (class "Default")
      (node (ref "Q2") (pin "3") (pinfunction "D_3") (pintype "passive"))
      (node (ref "T1") (pin "9") (pinfunction "D_9") (pintype "passive"))
      (node (ref "T2") (pin "9") (pinfunction "D_9") (pintype "passive"))
      (node (ref "T3") (pin "9") (pinfunction "D_9") (pintype "passive"))
      (node (ref "T4") (pin "9") (pinfunction "D_9") (pintype "passive"))
    )
    (net (code "164") (name "RDD") (class "Default")
      (node (ref "IC7") (pin "4") (pinfunction "C_4") (pintype "bidirectional"))
      (node (ref "JP4") (pin "12") (pinfunction "12_12") (pintype "passive"))
      (node (ref "R110") (pin "1") (pinfunction "1_1") (pintype "passive"))
    )
    (net (code "165") (name "RESET") (class "Default")
      (node (ref "IC1") (pin "63") (pinfunction "RESET_63") (pintype "input"))
      (node (ref "R30") (pin "1") (pinfunction "1_1") (pintype "passive"))
    )
    (net (code "166") (name "S-LED_1") (class "Default")
      (node (ref "JP4") (pin "1") (pinfunction "1_1") (pintype "passive"))
      (node (ref "R80") (pin "2") (pinfunction "2_2") (pintype "passive"))
    )
    (net (code "167") (name "S-LED_2") (class "Default")
      (node (ref "JP4") (pin "2") (pinfunction "2_2") (pintype "passive"))
      (node (ref "R111") (pin "2") (pinfunction "2_2") (pintype "passive"))
    )
    (net (code "168") (name "S-LED_3") (class "Default")
      (node (ref "JP4") (pin "3") (pinfunction "3_3") (pintype "passive"))
      (node (ref "R112") (pin "2") (pinfunction "2_2") (pintype "passive"))
    )
    (net (code "169") (name "S-LED_4") (class "Default")
      (node (ref "JP4") (pin "4") (pinfunction "4_4") (pintype "passive"))
      (node (ref "R113") (pin "2") (pinfunction "2_2") (pintype "passive"))
    )
    (net (code "170") (name "S-LED_5") (class "Default")
      (node (ref "JP4") (pin "5") (pinfunction "5_5") (pintype "passive"))
      (node (ref "R114") (pin "2") (pinfunction "2_2") (pintype "passive"))
    )
    (net (code "171") (name "S-LED_6") (class "Default")
      (node (ref "JP4") (pin "6") (pinfunction "6_6") (pintype "passive"))
      (node (ref "R115") (pin "2") (pinfunction "2_2") (pintype "passive"))
    )
    (net (code "172") (name "SCLK") (class "Default")
      (node (ref "IC1") (pin "46") (pinfunction "SCLK/RDXT_IN-_46") (pintype "bidirectional"))
      (node (ref "JP6") (pin "2") (pinfunction "2_2") (pintype "passive"))
    )
    (net (code "173") (name "SGNL1") (class "Default")
      (node (ref "JP4") (pin "11") (pinfunction "11_11") (pintype "passive"))
      (node (ref "R97") (pin "1") (pinfunction "1_1") (pintype "passive"))
    )
    (net (code "174") (name "SW") (class "Default")
      (node (ref "IC3") (pin "12") (pinfunction "SW_12") (pintype "power_in"))
      (node (ref "IC3") (pin "13") (pinfunction "SW_13") (pintype "power_in"))
      (node (ref "IC3") (pin "14") (pinfunction "SW_14") (pintype "power_in"))
      (node (ref "IC3") (pin "15") (pinfunction "SW_15") (pintype "power_in"))
      (node (ref "IC3") (pin "20") (pinfunction "SW_20") (pintype "power_in"))
      (node (ref "IC3") (pin "3") (pinfunction "SW_3") (pintype "power_in"))
      (node (ref "L1") (pin "1") (pinfunction "1_1") (pintype "power_in"))
      (node (ref "R108") (pin "2") (pinfunction "2_2") (pintype "passive"))
      (node (ref "R82") (pin "2") (pinfunction "2_2") (pintype "passive"))
      (node (ref "R83") (pin "1") (pinfunction "1_1") (pintype "passive"))
    )
    (net (code "175") (name "V+") (class "Default")
      (node (ref "D11") (pin "A") (pinfunction "A_A") (pintype "passive"))
      (node (ref "D21") (pin "K") (pinfunction "K_K") (pintype "passive"))
      (node (ref "IC7") (pin "1") (pinfunction "A_1") (pintype "bidirectional"))
      (node (ref "PACK-") (pin "1") (pinfunction "P$1_1") (pintype "passive"))
      (node (ref "R94") (pin "1") (pinfunction "1_1") (pintype "passive"))
      (node (ref "T3") (pin "2") (pinfunction "S_2") (pintype "passive"))
      (node (ref "T3") (pin "3") (pinfunction "S1_3") (pintype "passive"))
      (node (ref "T3") (pin "4") (pinfunction "S2_4") (pintype "passive"))
      (node (ref "T3") (pin "5") (pinfunction "S3_5") (pintype "passive"))
      (node (ref "T3") (pin "6") (pinfunction "S4_6") (pintype "passive"))
      (node (ref "T3") (pin "7") (pinfunction "S5_7") (pintype "passive"))
      (node (ref "T3") (pin "8") (pinfunction "S6_8") (pintype "passive"))
      (node (ref "T4") (pin "2") (pinfunction "S_2") (pintype "passive"))
      (node (ref "T4") (pin "3") (pinfunction "S1_3") (pintype "passive"))
      (node (ref "T4") (pin "4") (pinfunction "S2_4") (pintype "passive"))
      (node (ref "T4") (pin "5") (pinfunction "S3_5") (pintype "passive"))
      (node (ref "T4") (pin "6") (pinfunction "S4_6") (pintype "passive"))
      (node (ref "T4") (pin "7") (pinfunction "S5_7") (pintype "passive"))
      (node (ref "T4") (pin "8") (pinfunction "S6_8") (pintype "passive"))
    )
    (net (code "176") (name "V-") (class "Default")
      (node (ref "R81") (pin "1") (pinfunction "1_1") (pintype "passive"))
      (node (ref "R81") (pin "3") (pinfunction "1_3") (pintype "passive"))
      (node (ref "R84") (pin "1") (pinfunction "1_1") (pintype "passive"))
      (node (ref "R84") (pin "3") (pinfunction "1_3") (pintype "passive"))
      (node (ref "R92") (pin "1") (pinfunction "1_1") (pintype "passive"))
      (node (ref "T1") (pin "2") (pinfunction "S_2") (pintype "passive"))
      (node (ref "T1") (pin "3") (pinfunction "S1_3") (pintype "passive"))
      (node (ref "T1") (pin "4") (pinfunction "S2_4") (pintype "passive"))
      (node (ref "T1") (pin "5") (pinfunction "S3_5") (pintype "passive"))
      (node (ref "T1") (pin "6") (pinfunction "S4_6") (pintype "passive"))
      (node (ref "T1") (pin "7") (pinfunction "S5_7") (pintype "passive"))
      (node (ref "T1") (pin "8") (pinfunction "S6_8") (pintype "passive"))
      (node (ref "T2") (pin "2") (pinfunction "S_2") (pintype "passive"))
      (node (ref "T2") (pin "3") (pinfunction "S1_3") (pintype "passive"))
      (node (ref "T2") (pin "4") (pinfunction "S2_4") (pintype "passive"))
      (node (ref "T2") (pin "5") (pinfunction "S3_5") (pintype "passive"))
      (node (ref "T2") (pin "6") (pinfunction "S4_6") (pintype "passive"))
      (node (ref "T2") (pin "7") (pinfunction "S5_7") (pintype "passive"))
      (node (ref "T2") (pin "8") (pinfunction "S6_8") (pintype "passive"))
    )
    (net (code "177") (name "VCOM") (class "Default")
      (node (ref "C22") (pin "1") (pinfunction "1_1") (pintype "passive"))
      (node (ref "C79") (pin "1") (pinfunction "1_1") (pintype "passive"))
      (node (ref "IC1") (pin "43") (pinfunction "VCOM_43") (pintype "output"))
      (node (ref "R29") (pin "2") (pinfunction "2_2") (pintype "passive"))
      (node (ref "R64") (pin "2") (pinfunction "2_2") (pintype "passive"))
      (node (ref "R65") (pin "2") (pinfunction "2_2") (pintype "passive"))
      (node (ref "R67") (pin "2") (pinfunction "2_2") (pintype "passive"))
      (node (ref "R68") (pin "2") (pinfunction "2_2") (pintype "passive"))
      (node (ref "R69") (pin "2") (pinfunction "2_2") (pintype "passive"))
      (node (ref "R70") (pin "2") (pinfunction "2_2") (pintype "passive"))
      (node (ref "R71") (pin "2") (pinfunction "2_2") (pintype "passive"))
    )
    (net (code "178") (name "VIN") (class "Default")
      (node (ref "R107") (pin "2") (pinfunction "2_2") (pintype "passive"))
      (node (ref "R90") (pin "2") (pinfunction "2_2") (pintype "passive"))
    )
    (net (code "179") (name "VPWR") (class "Default")
      (node (ref "C61") (pin "1") (pinfunction "1_1") (pintype "passive"))
      (node (ref "D1") (pin "K") (pinfunction "K_K") (pintype "passive"))
      (node (ref "D2") (pin "K") (pinfunction "K_K") (pintype "passive"))
      (node (ref "D20") (pin "K") (pinfunction "K_K") (pintype "passive"))
      (node (ref "D4") (pin "K") (pinfunction "K_K") (pintype "passive"))
      (node (ref "D5") (pin "K") (pinfunction "K_K") (pintype "passive"))
      (node (ref "IC1") (pin "1") (pinfunction "VPWR2_1") (pintype "input"))
      (node (ref "IC1") (pin "2") (pinfunction "VPWR1_2") (pintype "input"))
      (node (ref "R66") (pin "2") (pinfunction "2_2") (pintype "passive"))
    )
    (net (code "180") (name "WAKE") (class "Default")
      (node (ref "C78") (pin "2") (pinfunction "2_2") (pintype "passive"))
      (node (ref "D16") (pin "K") (pinfunction "K_K") (pintype "passive"))
      (node (ref "JP6") (pin "13") (pinfunction "13_13") (pintype "passive"))
      (node (ref "R100") (pin "1") (pinfunction "1_1") (pintype "passive"))
      (node (ref "R99") (pin "2") (pinfunction "2_2") (pintype "passive"))
      (node (ref "WAKE") (pin "P$1") (pinfunction "P$1_P$1") (pintype "passive"))
    )
    (net (code "181") (name "unconnected-(IC1-RDTX_OUT+-Pad48)") (class "Default")
      (node (ref "IC1") (pin "48") (pinfunction "RDTX_OUT+_48") (pintype "bidirectional"))
    )
    (net (code "182") (name "unconnected-(IC1-RDTX_OUT--Pad45)") (class "Default")
      (node (ref "IC1") (pin "45") (pinfunction "RDTX_OUT-_45") (pintype "bidirectional"))
    )
    (net (code "183") (name "unconnected-(IC1-SCL-Pad61)") (class "Default")
      (node (ref "IC1") (pin "61") (pinfunction "SCL_61") (pintype "bidirectional"))
    )
    (net (code "184") (name "unconnected-(IC1-SDA-Pad62)") (class "Default")
      (node (ref "IC1") (pin "62") (pinfunction "SDA_62") (pintype "bidirectional"))
    )
    (net (code "185") (name "unconnected-(IC3-PG-Pad32)") (class "Default")
      (node (ref "IC3") (pin "32") (pinfunction "PG_32") (pintype "output"))
    )
  )
)
